# Thermister_Expansion_Module.net
KiCad netlist of a schematic drawn in EAGLE
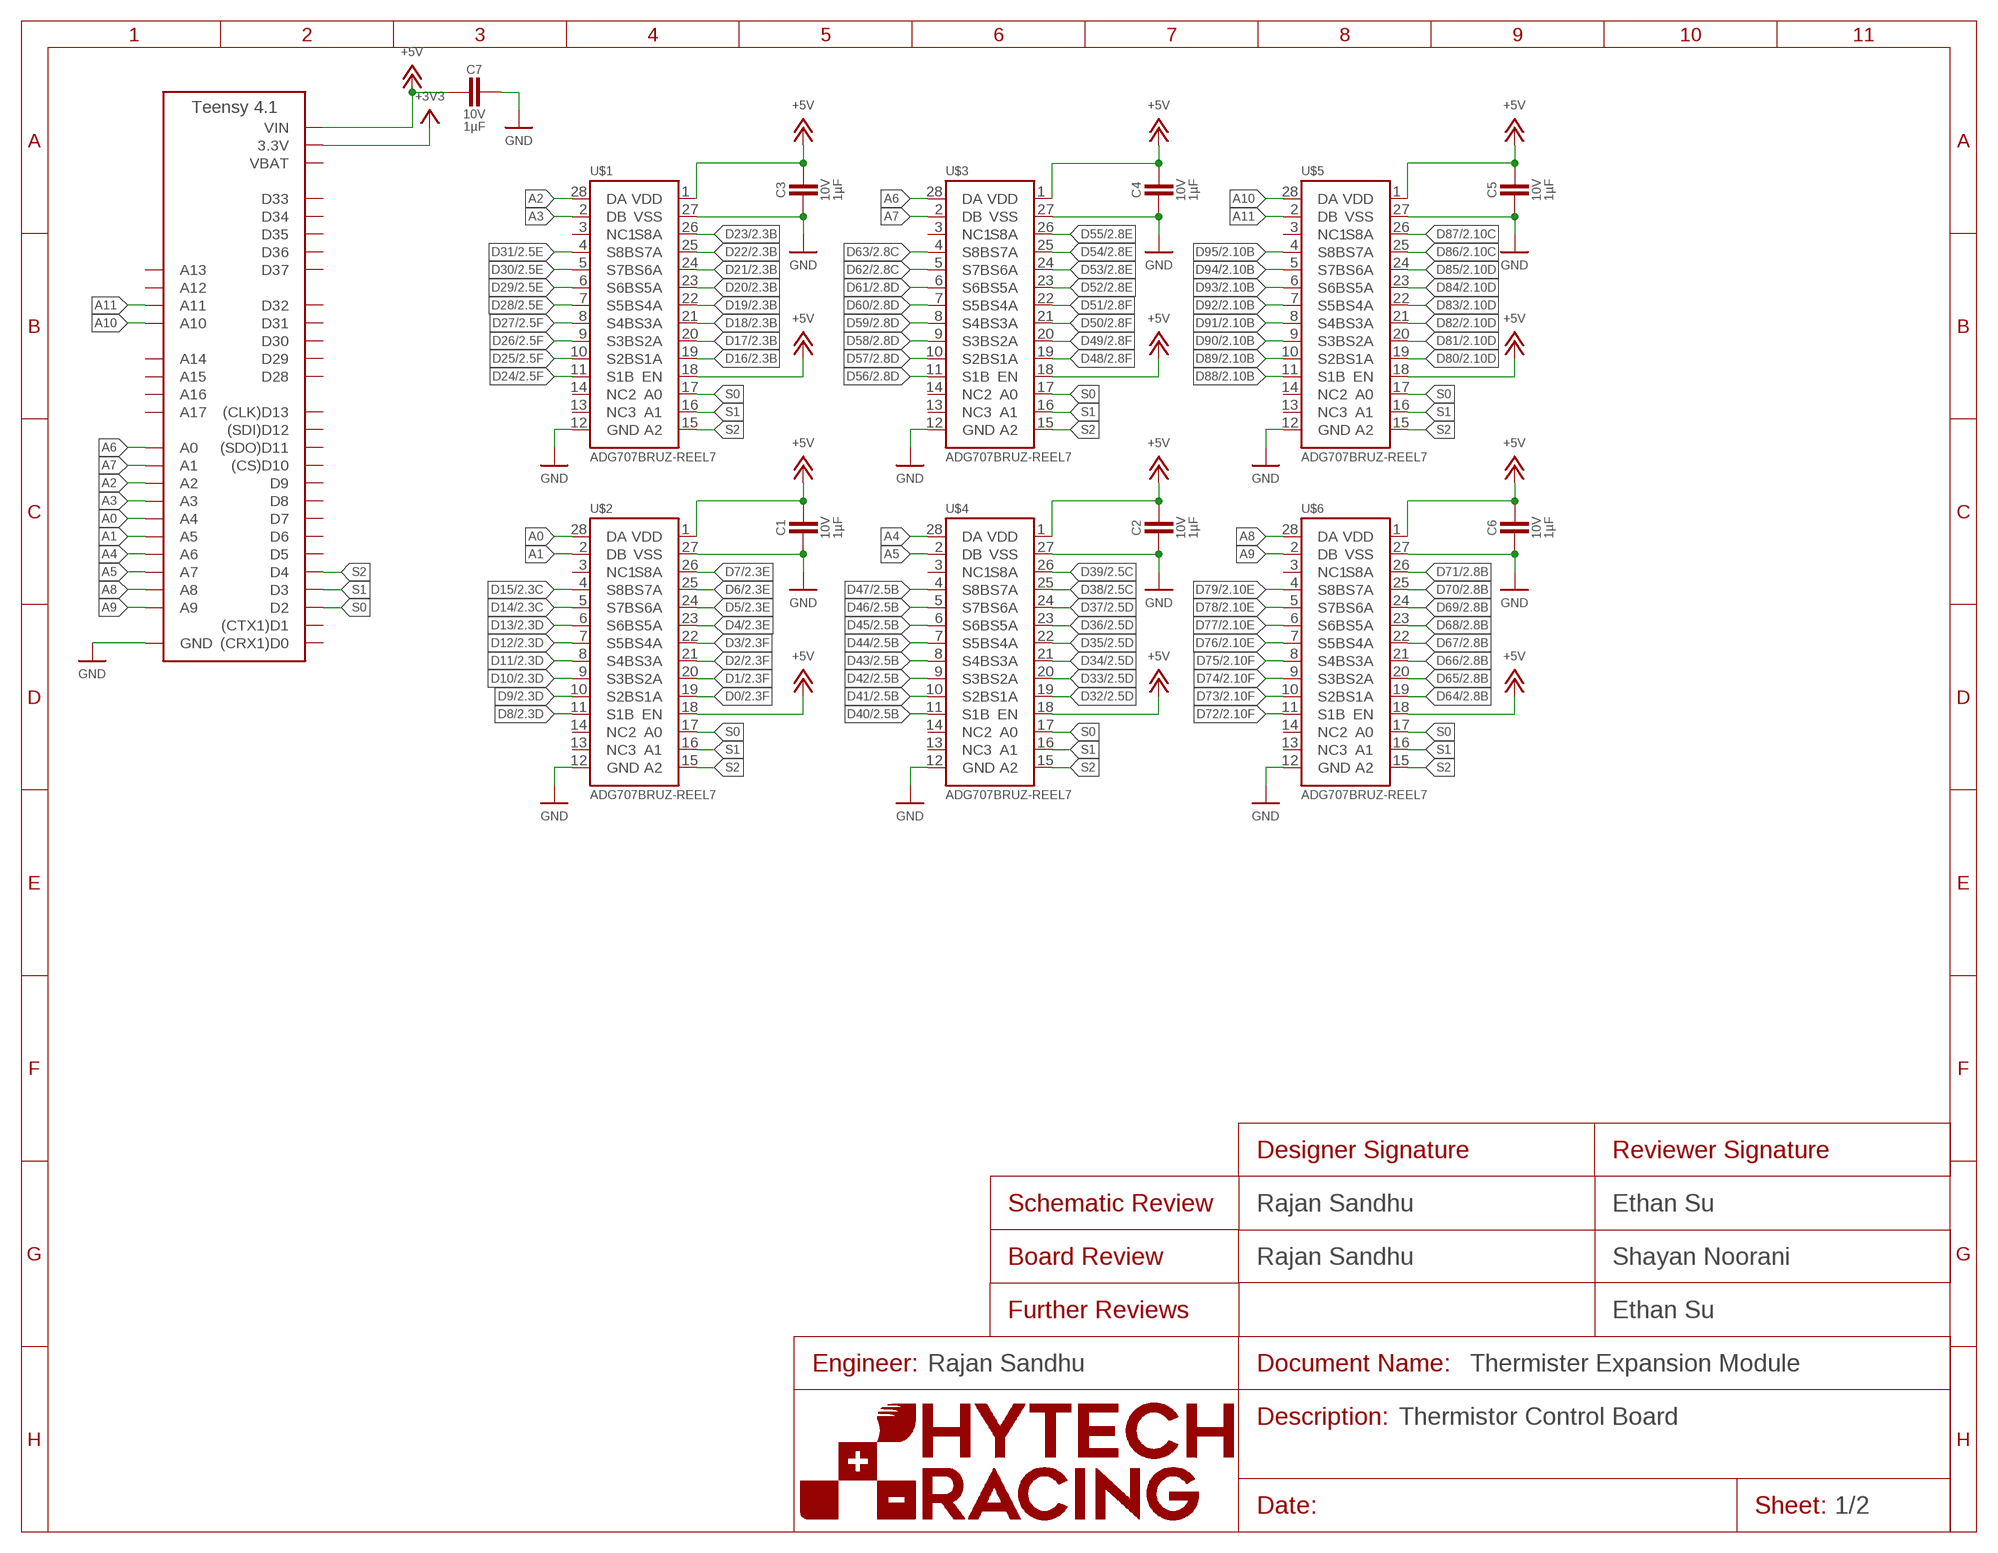
[diagram p0: schematic, sheet 1]
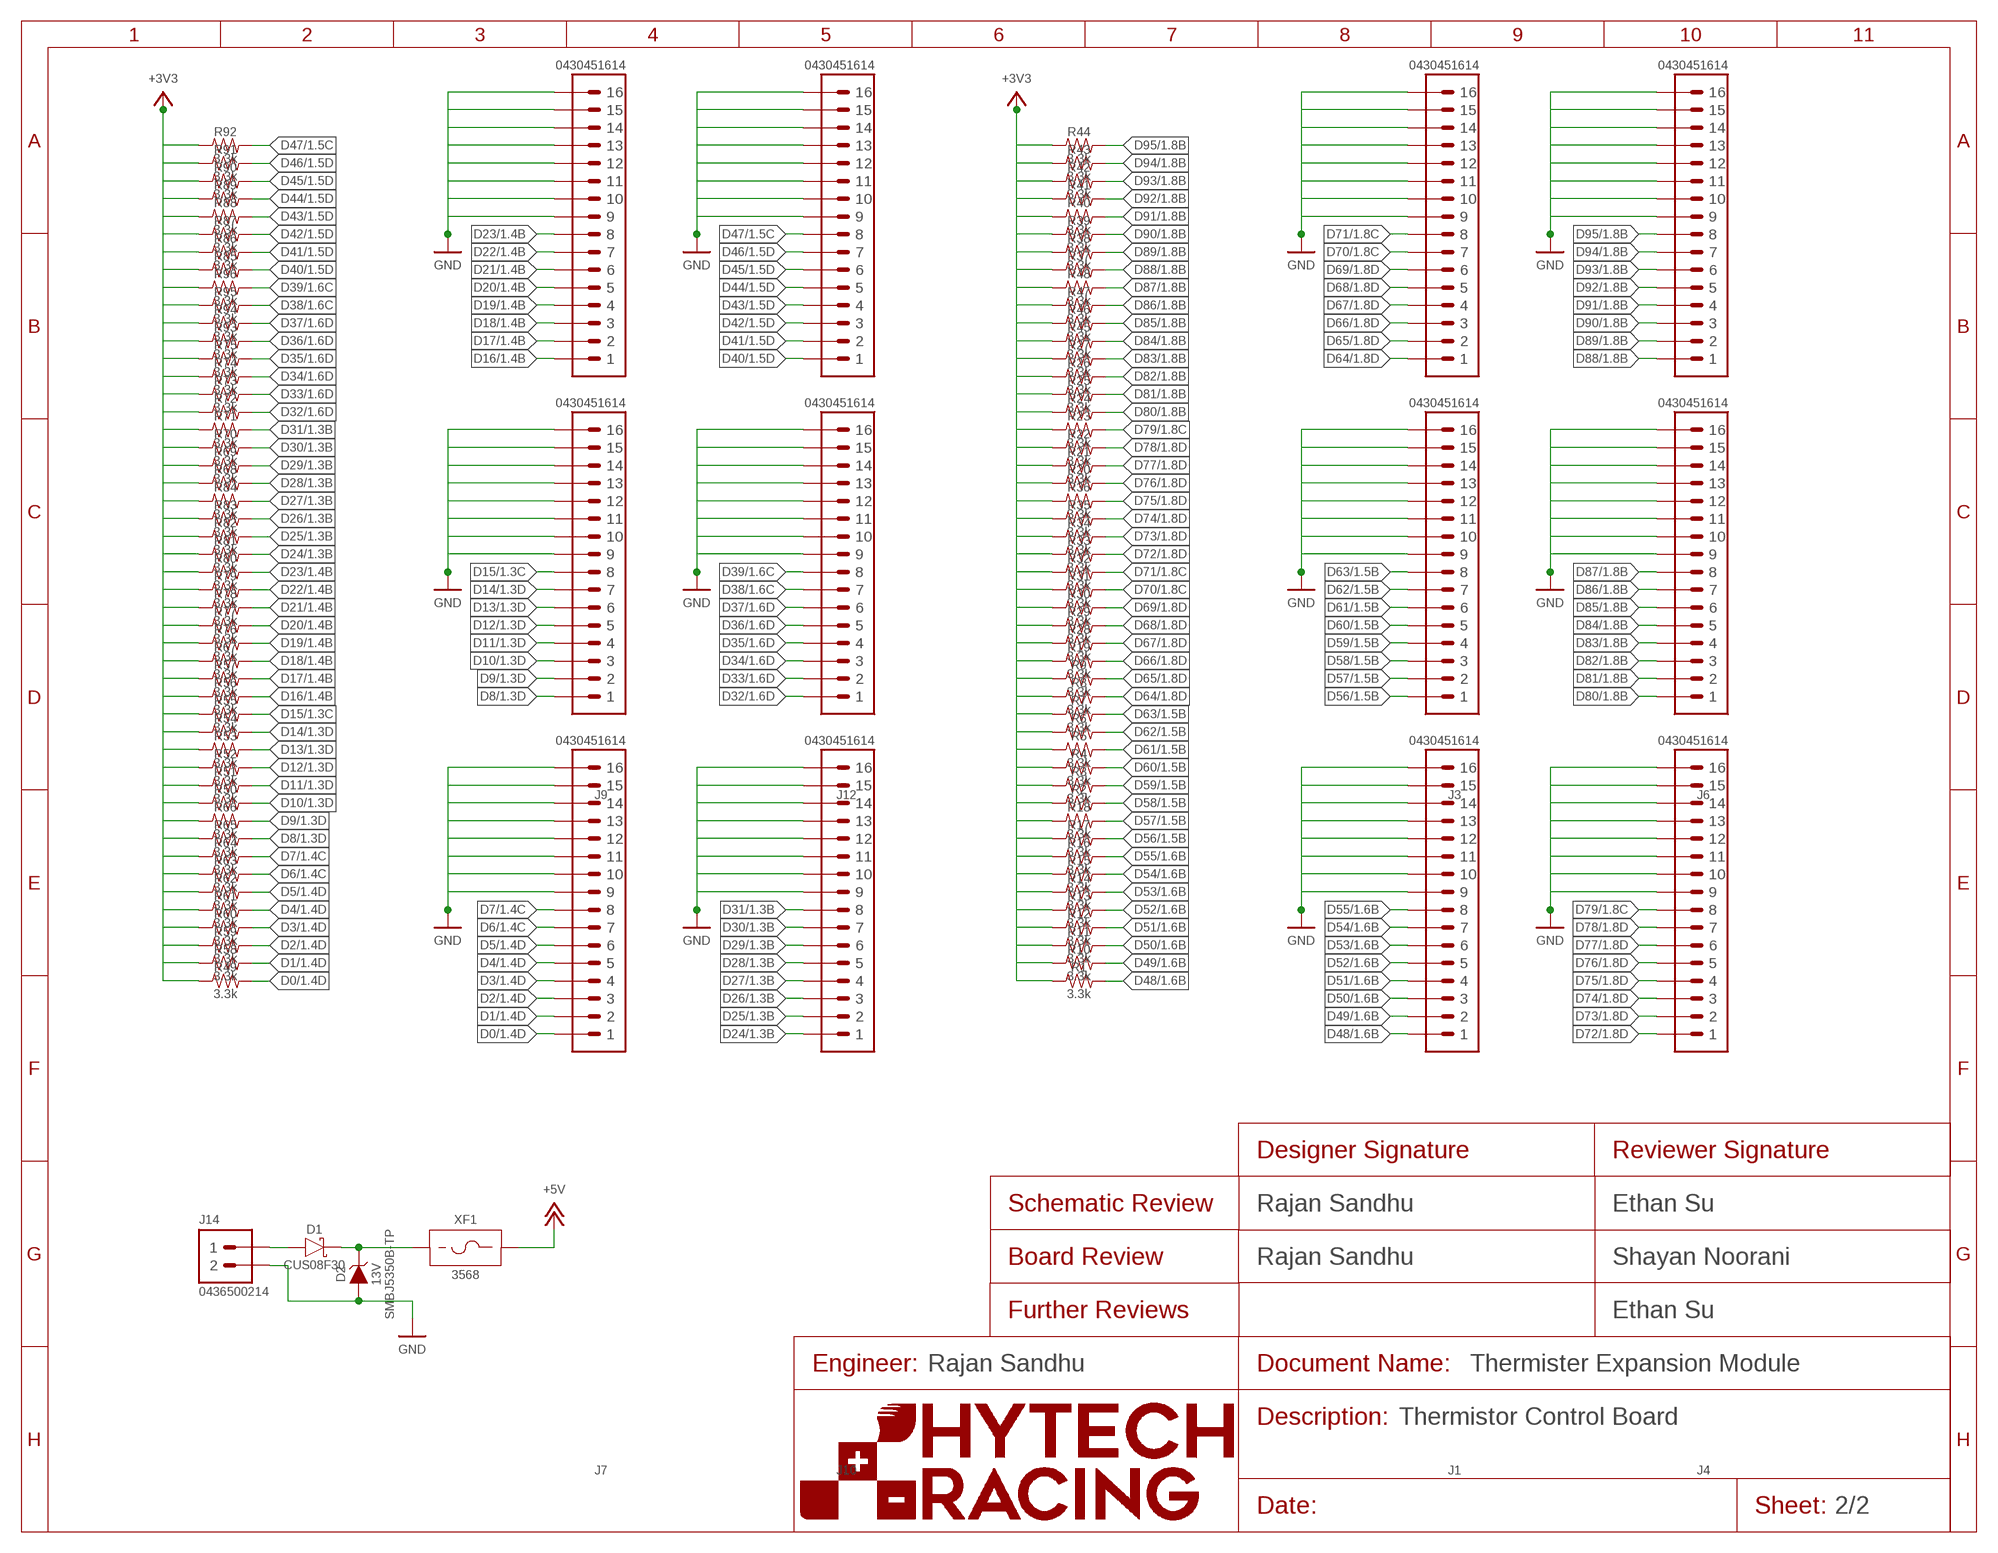
[diagram p1: schematic, sheet 2]

(export (version "E")
  (design (tool "Eeschema 10.0.6"))
  (components
    (comp (ref "D1")
      (value "SCHOTTKY_SOD323_30V")
      (footprint "eagle-import:SOD-323")
      (fields
        (field (name "MANUFACTURER") "Toshiba Semiconductor and Storage")
        (field (name "MPN") "CUS08F30")
        (field (name "VOLTAGE") "30V")
      )
      (libsource (lib "eagle-import") (part "SCHOTTKY_?_SOD32330V"))
    )
    (comp (ref "D2")
      (value "ZENER_SMB(DO-214AA)_13V")
      (footprint "eagle-import:SMB(DO-214AA)")
      (fields
        (field (name "MANUFACTURER") "Micro Commercial Co")
        (field (name "MPN") "SMBJ5350B-TP")
        (field (name "VOLTAGE") "13V")
      )
      (libsource (lib "eagle-import") (part "ZENER_?_SMB(DO-214AA)13V"))
    )
    (comp (ref "J1")
      (value "CONNECTOR-16_MF_T_V_")
      (footprint "eagle-import:MOLEX_MICROFIT_PTH_VERTICAL_16_DUAL")
      (fields (field (name "MPN") "0430451614") (field (name "MANUFACTURER") "MOLEX"))
      (libsource (lib "eagle-import") (part "CONNECTOR-16_?_MF_T_V"))
    )
    (comp (ref "J2")
      (value "CONNECTOR-16_MF_T_V_")
      (footprint "eagle-import:MOLEX_MICROFIT_PTH_VERTICAL_16_DUAL")
      (fields (field (name "MPN") "0430451614") (field (name "MANUFACTURER") "MOLEX"))
      (libsource (lib "eagle-import") (part "CONNECTOR-16_?_MF_T_V"))
    )
    (comp (ref "J3")
      (value "CONNECTOR-16_MF_T_V_")
      (footprint "eagle-import:MOLEX_MICROFIT_PTH_VERTICAL_16_DUAL")
      (fields (field (name "MPN") "0430451614") (field (name "MANUFACTURER") "MOLEX"))
      (libsource (lib "eagle-import") (part "CONNECTOR-16_?_MF_T_V"))
    )
    (comp (ref "J4")
      (value "CONNECTOR-16_MF_T_V_")
      (footprint "eagle-import:MOLEX_MICROFIT_PTH_VERTICAL_16_DUAL")
      (fields (field (name "MPN") "0430451614") (field (name "MANUFACTURER") "MOLEX"))
      (libsource (lib "eagle-import") (part "CONNECTOR-16_?_MF_T_V"))
    )
    (comp (ref "J5")
      (value "CONNECTOR-16_MF_T_V_")
      (footprint "eagle-import:MOLEX_MICROFIT_PTH_VERTICAL_16_DUAL")
      (fields (field (name "MPN") "0430451614") (field (name "MANUFACTURER") "MOLEX"))
      (libsource (lib "eagle-import") (part "CONNECTOR-16_?_MF_T_V"))
    )
    (comp (ref "J6")
      (value "CONNECTOR-16_MF_T_V_")
      (footprint "eagle-import:MOLEX_MICROFIT_PTH_VERTICAL_16_DUAL")
      (fields (field (name "MPN") "0430451614") (field (name "MANUFACTURER") "MOLEX"))
      (libsource (lib "eagle-import") (part "CONNECTOR-16_?_MF_T_V"))
    )
    (comp (ref "J7")
      (value "CONNECTOR-16_MF_T_V_")
      (footprint "eagle-import:MOLEX_MICROFIT_PTH_VERTICAL_16_DUAL")
      (fields (field (name "MPN") "0430451614") (field (name "MANUFACTURER") "MOLEX"))
      (libsource (lib "eagle-import") (part "CONNECTOR-16_?_MF_T_V"))
    )
    (comp (ref "J8")
      (value "CONNECTOR-16_MF_T_V_")
      (footprint "eagle-import:MOLEX_MICROFIT_PTH_VERTICAL_16_DUAL")
      (fields (field (name "MPN") "0430451614") (field (name "MANUFACTURER") "MOLEX"))
      (libsource (lib "eagle-import") (part "CONNECTOR-16_?_MF_T_V"))
    )
    (comp (ref "J9")
      (value "CONNECTOR-16_MF_T_V_")
      (footprint "eagle-import:MOLEX_MICROFIT_PTH_VERTICAL_16_DUAL")
      (fields (field (name "MPN") "0430451614") (field (name "MANUFACTURER") "MOLEX"))
      (libsource (lib "eagle-import") (part "CONNECTOR-16_?_MF_T_V"))
    )
    (comp (ref "J10")
      (value "CONNECTOR-16_MF_T_V_")
      (footprint "eagle-import:MOLEX_MICROFIT_PTH_VERTICAL_16_DUAL")
      (fields (field (name "MPN") "0430451614") (field (name "MANUFACTURER") "MOLEX"))
      (libsource (lib "eagle-import") (part "CONNECTOR-16_?_MF_T_V"))
    )
    (comp (ref "J11")
      (value "CONNECTOR-16_MF_T_V_")
      (footprint "eagle-import:MOLEX_MICROFIT_PTH_VERTICAL_16_DUAL")
      (fields (field (name "MPN") "0430451614") (field (name "MANUFACTURER") "MOLEX"))
      (libsource (lib "eagle-import") (part "CONNECTOR-16_?_MF_T_V"))
    )
    (comp (ref "J12")
      (value "CONNECTOR-16_MF_T_V_")
      (footprint "eagle-import:MOLEX_MICROFIT_PTH_VERTICAL_16_DUAL")
      (fields (field (name "MPN") "0430451614") (field (name "MANUFACTURER") "MOLEX"))
      (libsource (lib "eagle-import") (part "CONNECTOR-16_?_MF_T_V"))
    )
    (comp (ref "J14")
      (value "CONNECTOR-2_MICROFIT_SMD_RIGHTANGLE_02_SINGLE_BLACK")
      (footprint "eagle-import:MOLEX_MICROFIT_SMD_RIGHTANGLE_02_SINGLE")
      (fields (field (name "MANUFACTURER") "Molex") (field (name "MPN") "0436500214"))
      (libsource (lib "eagle-import") (part "CONNECTOR-2_?_MICROFIT_SMD_RIGHTANGLE_02_SINGLEBLACK"))
    )
    (comp (ref "R1")
      (value "RESISTOR_0603_3.3K")
      (footprint "eagle-import:0603-RES")
      (fields
        (field (name "MANUFACTURER") "Panasonic Electronic Components")
        (field (name "MPN") "ERJ-PB3D3301V")
        (field (name "POWER") "0.3W")
        (field (name "RESISTANCE") "3.3k")
      )
      (libsource (lib "eagle-import") (part "RESISTOR_?_06033.3K"))
    )
    (comp (ref "R2")
      (value "RESISTOR_0603_3.3K")
      (footprint "eagle-import:0603-RES")
      (fields
        (field (name "MANUFACTURER") "Panasonic Electronic Components")
        (field (name "MPN") "ERJ-PB3D3301V")
        (field (name "POWER") "0.3W")
      )
      (libsource (lib "eagle-import") (part "RESISTOR_?_06033.3K"))
    )
    (comp (ref "R3")
      (value "RESISTOR_0603_3.3K")
      (footprint "eagle-import:0603-RES")
      (fields
        (field (name "MANUFACTURER") "Panasonic Electronic Components")
        (field (name "MPN") "ERJ-PB3D3301V")
        (field (name "POWER") "0.3W")
        (field (name "RESISTANCE") "3.3k")
      )
      (libsource (lib "eagle-import") (part "RESISTOR_?_06033.3K"))
    )
    (comp (ref "R4")
      (value "RESISTOR_0603_3.3K")
      (footprint "eagle-import:0603-RES")
      (fields
        (field (name "MANUFACTURER") "Panasonic Electronic Components")
        (field (name "MPN") "ERJ-PB3D3301V")
        (field (name "POWER") "0.3W")
        (field (name "RESISTANCE") "3.3k")
      )
      (libsource (lib "eagle-import") (part "RESISTOR_?_06033.3K"))
    )
    (comp (ref "R5")
      (value "RESISTOR_0603_3.3K")
      (footprint "eagle-import:0603-RES")
      (fields
        (field (name "MANUFACTURER") "Panasonic Electronic Components")
        (field (name "MPN") "ERJ-PB3D3301V")
        (field (name "POWER") "0.3W")
        (field (name "RESISTANCE") "3.3k")
      )
      (libsource (lib "eagle-import") (part "RESISTOR_?_06033.3K"))
    )
    (comp (ref "R6")
      (value "RESISTOR_0603_3.3K")
      (footprint "eagle-import:0603-RES")
      (fields
        (field (name "MANUFACTURER") "Panasonic Electronic Components")
        (field (name "MPN") "ERJ-PB3D3301V")
        (field (name "POWER") "0.3W")
      )
      (libsource (lib "eagle-import") (part "RESISTOR_?_06033.3K"))
    )
    (comp (ref "R7")
      (value "RESISTOR_0603_3.3K")
      (footprint "eagle-import:0603-RES")
      (fields
        (field (name "MANUFACTURER") "Panasonic Electronic Components")
        (field (name "MPN") "ERJ-PB3D3301V")
        (field (name "POWER") "0.3W")
        (field (name "RESISTANCE") "3.3k")
      )
      (libsource (lib "eagle-import") (part "RESISTOR_?_06033.3K"))
    )
    (comp (ref "R8")
      (value "RESISTOR_0603_3.3K")
      (footprint "eagle-import:0603-RES")
      (fields
        (field (name "MANUFACTURER") "Panasonic Electronic Components")
        (field (name "MPN") "ERJ-PB3D3301V")
        (field (name "POWER") "0.3W")
        (field (name "RESISTANCE") "3.3k")
      )
      (libsource (lib "eagle-import") (part "RESISTOR_?_06033.3K"))
    )
    (comp (ref "R9")
      (value "RESISTOR_0603_3.3K")
      (footprint "eagle-import:0603-RES")
      (fields
        (field (name "MANUFACTURER") "Panasonic Electronic Components")
        (field (name "MPN") "ERJ-PB3D3301V")
        (field (name "POWER") "0.3W")
        (field (name "RESISTANCE") "3.3k")
      )
      (libsource (lib "eagle-import") (part "RESISTOR_?_06033.3K"))
    )
    (comp (ref "R10")
      (value "RESISTOR_0603_3.3K")
      (footprint "eagle-import:0603-RES")
      (fields
        (field (name "MANUFACTURER") "Panasonic Electronic Components")
        (field (name "MPN") "ERJ-PB3D3301V")
        (field (name "POWER") "0.3W")
        (field (name "RESISTANCE") "3.3k")
      )
      (libsource (lib "eagle-import") (part "RESISTOR_?_06033.3K"))
    )
    (comp (ref "R11")
      (value "RESISTOR_0603_3.3K")
      (footprint "eagle-import:0603-RES")
      (fields
        (field (name "MANUFACTURER") "Panasonic Electronic Components")
        (field (name "MPN") "ERJ-PB3D3301V")
        (field (name "POWER") "0.3W")
        (field (name "RESISTANCE") "3.3k")
      )
      (libsource (lib "eagle-import") (part "RESISTOR_?_06033.3K"))
    )
    (comp (ref "R12")
      (value "RESISTOR_0603_3.3K")
      (footprint "eagle-import:0603-RES")
      (fields
        (field (name "MANUFACTURER") "Panasonic Electronic Components")
        (field (name "MPN") "ERJ-PB3D3301V")
        (field (name "POWER") "0.3W")
        (field (name "RESISTANCE") "3.3k")
      )
      (libsource (lib "eagle-import") (part "RESISTOR_?_06033.3K"))
    )
    (comp (ref "R13")
      (value "RESISTOR_0603_3.3K")
      (footprint "eagle-import:0603-RES")
      (fields
        (field (name "MANUFACTURER") "Panasonic Electronic Components")
        (field (name "MPN") "ERJ-PB3D3301V")
        (field (name "POWER") "0.3W")
        (field (name "RESISTANCE") "3.3k")
      )
      (libsource (lib "eagle-import") (part "RESISTOR_?_06033.3K"))
    )
    (comp (ref "R14")
      (value "RESISTOR_0603_3.3K")
      (footprint "eagle-import:0603-RES")
      (fields
        (field (name "MANUFACTURER") "Panasonic Electronic Components")
        (field (name "MPN") "ERJ-PB3D3301V")
        (field (name "POWER") "0.3W")
        (field (name "RESISTANCE") "3.3k")
      )
      (libsource (lib "eagle-import") (part "RESISTOR_?_06033.3K"))
    )
    (comp (ref "R15")
      (value "RESISTOR_0603_3.3K")
      (footprint "eagle-import:0603-RES")
      (fields
        (field (name "MANUFACTURER") "Panasonic Electronic Components")
        (field (name "MPN") "ERJ-PB3D3301V")
        (field (name "POWER") "0.3W")
        (field (name "RESISTANCE") "3.3k")
      )
      (libsource (lib "eagle-import") (part "RESISTOR_?_06033.3K"))
    )
    (comp (ref "R16")
      (value "RESISTOR_0603_3.3K")
      (footprint "eagle-import:0603-RES")
      (fields
        (field (name "MANUFACTURER") "Panasonic Electronic Components")
        (field (name "MPN") "ERJ-PB3D3301V")
        (field (name "POWER") "0.3W")
        (field (name "RESISTANCE") "3.3k")
      )
      (libsource (lib "eagle-import") (part "RESISTOR_?_06033.3K"))
    )
    (comp (ref "R17")
      (value "RESISTOR_0603_3.3K")
      (footprint "eagle-import:0603-RES")
      (fields
        (field (name "MANUFACTURER") "Panasonic Electronic Components")
        (field (name "MPN") "ERJ-PB3D3301V")
        (field (name "POWER") "0.3W")
        (field (name "RESISTANCE") "3.3k")
      )
      (libsource (lib "eagle-import") (part "RESISTOR_?_06033.3K"))
    )
    (comp (ref "R18")
      (value "RESISTOR_0603_3.3K")
      (footprint "eagle-import:0603-RES")
      (fields
        (field (name "MANUFACTURER") "Panasonic Electronic Components")
        (field (name "MPN") "ERJ-PB3D3301V")
        (field (name "POWER") "0.3W")
        (field (name "RESISTANCE") "3.3k")
      )
      (libsource (lib "eagle-import") (part "RESISTOR_?_06033.3K"))
    )
    (comp (ref "R19")
      (value "RESISTOR_0603_3.3K")
      (footprint "eagle-import:0603-RES")
      (fields
        (field (name "MANUFACTURER") "Panasonic Electronic Components")
        (field (name "MPN") "ERJ-PB3D3301V")
        (field (name "POWER") "0.3W")
        (field (name "RESISTANCE") "3.3k")
      )
      (libsource (lib "eagle-import") (part "RESISTOR_?_06033.3K"))
    )
    (comp (ref "R20")
      (value "RESISTOR_0603_3.3K")
      (footprint "eagle-import:0603-RES")
      (fields
        (field (name "MANUFACTURER") "Panasonic Electronic Components")
        (field (name "MPN") "ERJ-PB3D3301V")
        (field (name "POWER") "0.3W")
      )
      (libsource (lib "eagle-import") (part "RESISTOR_?_06033.3K"))
    )
    (comp (ref "R21")
      (value "RESISTOR_0603_3.3K")
      (footprint "eagle-import:0603-RES")
      (fields
        (field (name "MANUFACTURER") "Panasonic Electronic Components")
        (field (name "MPN") "ERJ-PB3D3301V")
        (field (name "POWER") "0.3W")
        (field (name "RESISTANCE") "3.3k")
      )
      (libsource (lib "eagle-import") (part "RESISTOR_?_06033.3K"))
    )
    (comp (ref "R22")
      (value "RESISTOR_0603_3.3K")
      (footprint "eagle-import:0603-RES")
      (fields
        (field (name "MANUFACTURER") "Panasonic Electronic Components")
        (field (name "MPN") "ERJ-PB3D3301V")
        (field (name "POWER") "0.3W")
        (field (name "RESISTANCE") "3.3k")
      )
      (libsource (lib "eagle-import") (part "RESISTOR_?_06033.3K"))
    )
    (comp (ref "R23")
      (value "RESISTOR_0603_3.3K")
      (footprint "eagle-import:0603-RES")
      (fields
        (field (name "MANUFACTURER") "Panasonic Electronic Components")
        (field (name "MPN") "ERJ-PB3D3301V")
        (field (name "POWER") "0.3W")
        (field (name "RESISTANCE") "3.3k")
      )
      (libsource (lib "eagle-import") (part "RESISTOR_?_06033.3K"))
    )
    (comp (ref "R24")
      (value "RESISTOR_0603_3.3K")
      (footprint "eagle-import:0603-RES")
      (fields
        (field (name "MANUFACTURER") "Panasonic Electronic Components")
        (field (name "MPN") "ERJ-PB3D3301V")
        (field (name "POWER") "0.3W")
      )
      (libsource (lib "eagle-import") (part "RESISTOR_?_06033.3K"))
    )
    (comp (ref "R25")
      (value "RESISTOR_0603_3.3K")
      (footprint "eagle-import:0603-RES")
      (fields
        (field (name "MANUFACTURER") "Panasonic Electronic Components")
        (field (name "MPN") "ERJ-PB3D3301V")
        (field (name "POWER") "0.3W")
        (field (name "RESISTANCE") "3.3k")
      )
      (libsource (lib "eagle-import") (part "RESISTOR_?_06033.3K"))
    )
    (comp (ref "R26")
      (value "RESISTOR_0603_3.3K")
      (footprint "eagle-import:0603-RES")
      (fields
        (field (name "MANUFACTURER") "Panasonic Electronic Components")
        (field (name "MPN") "ERJ-PB3D3301V")
        (field (name "POWER") "0.3W")
        (field (name "RESISTANCE") "3.3k")
      )
      (libsource (lib "eagle-import") (part "RESISTOR_?_06033.3K"))
    )
    (comp (ref "R27")
      (value "RESISTOR_0603_3.3K")
      (footprint "eagle-import:0603-RES")
      (fields
        (field (name "MANUFACTURER") "Panasonic Electronic Components")
        (field (name "MPN") "ERJ-PB3D3301V")
        (field (name "POWER") "0.3W")
        (field (name "RESISTANCE") "3.3k")
      )
      (libsource (lib "eagle-import") (part "RESISTOR_?_06033.3K"))
    )
    (comp (ref "R28")
      (value "RESISTOR_0603_3.3K")
      (footprint "eagle-import:0603-RES")
      (fields
        (field (name "MANUFACTURER") "Panasonic Electronic Components")
        (field (name "MPN") "ERJ-PB3D3301V")
        (field (name "POWER") "0.3W")
        (field (name "RESISTANCE") "3.3k")
      )
      (libsource (lib "eagle-import") (part "RESISTOR_?_06033.3K"))
    )
    (comp (ref "R29")
      (value "RESISTOR_0603_3.3K")
      (footprint "eagle-import:0603-RES")
      (fields
        (field (name "MANUFACTURER") "Panasonic Electronic Components")
        (field (name "MPN") "ERJ-PB3D3301V")
        (field (name "POWER") "0.3W")
        (field (name "RESISTANCE") "3.3k")
      )
      (libsource (lib "eagle-import") (part "RESISTOR_?_06033.3K"))
    )
    (comp (ref "R30")
      (value "RESISTOR_0603_3.3K")
      (footprint "eagle-import:0603-RES")
      (fields
        (field (name "MANUFACTURER") "Panasonic Electronic Components")
        (field (name "MPN") "ERJ-PB3D3301V")
        (field (name "POWER") "0.3W")
        (field (name "RESISTANCE") "3.3k")
      )
      (libsource (lib "eagle-import") (part "RESISTOR_?_06033.3K"))
    )
    (comp (ref "R31")
      (value "RESISTOR_0603_3.3K")
      (footprint "eagle-import:0603-RES")
      (fields
        (field (name "MANUFACTURER") "Panasonic Electronic Components")
        (field (name "MPN") "ERJ-PB3D3301V")
        (field (name "POWER") "0.3W")
        (field (name "RESISTANCE") "3.3k")
      )
      (libsource (lib "eagle-import") (part "RESISTOR_?_06033.3K"))
    )
    (comp (ref "R32")
      (value "RESISTOR_0603_3.3K")
      (footprint "eagle-import:0603-RES")
      (fields
        (field (name "MANUFACTURER") "Panasonic Electronic Components")
        (field (name "MPN") "ERJ-PB3D3301V")
        (field (name "POWER") "0.3W")
        (field (name "RESISTANCE") "3.3k")
      )
      (libsource (lib "eagle-import") (part "RESISTOR_?_06033.3K"))
    )
    (comp (ref "R33")
      (value "RESISTOR_0603_3.3K")
      (footprint "eagle-import:0603-RES")
      (fields
        (field (name "MANUFACTURER") "Panasonic Electronic Components")
        (field (name "MPN") "ERJ-PB3D3301V")
        (field (name "POWER") "0.3W")
        (field (name "RESISTANCE") "3.3k")
      )
      (libsource (lib "eagle-import") (part "RESISTOR_?_06033.3K"))
    )
    (comp (ref "R34")
      (value "RESISTOR_0603_3.3K")
      (footprint "eagle-import:0603-RES")
      (fields
        (field (name "MANUFACTURER") "Panasonic Electronic Components")
        (field (name "MPN") "ERJ-PB3D3301V")
        (field (name "POWER") "0.3W")
        (field (name "RESISTANCE") "3.3k")
      )
      (libsource (lib "eagle-import") (part "RESISTOR_?_06033.3K"))
    )
    (comp (ref "R35")
      (value "RESISTOR_0603_3.3K")
      (footprint "eagle-import:0603-RES")
      (fields
        (field (name "MANUFACTURER") "Panasonic Electronic Components")
        (field (name "MPN") "ERJ-PB3D3301V")
        (field (name "POWER") "0.3W")
        (field (name "RESISTANCE") "3.3k")
      )
      (libsource (lib "eagle-import") (part "RESISTOR_?_06033.3K"))
    )
    (comp (ref "R36")
      (value "RESISTOR_0603_3.3K")
      (footprint "eagle-import:0603-RES")
      (fields
        (field (name "MANUFACTURER") "Panasonic Electronic Components")
        (field (name "MPN") "ERJ-PB3D3301V")
        (field (name "POWER") "0.3W")
        (field (name "RESISTANCE") "3.3k")
      )
      (libsource (lib "eagle-import") (part "RESISTOR_?_06033.3K"))
    )
    (comp (ref "R37")
      (value "RESISTOR_0603_3.3K")
      (footprint "eagle-import:0603-RES")
      (fields
        (field (name "MANUFACTURER") "Panasonic Electronic Components")
        (field (name "MPN") "ERJ-PB3D3301V")
        (field (name "POWER") "0.3W")
      )
      (libsource (lib "eagle-import") (part "RESISTOR_?_06033.3K"))
    )
    (comp (ref "R38")
      (value "RESISTOR_0603_3.3K")
      (footprint "eagle-import:0603-RES")
      (fields
        (field (name "MANUFACTURER") "Panasonic Electronic Components")
        (field (name "MPN") "ERJ-PB3D3301V")
        (field (name "POWER") "0.3W")
        (field (name "RESISTANCE") "3.3k")
      )
      (libsource (lib "eagle-import") (part "RESISTOR_?_06033.3K"))
    )
    (comp (ref "R39")
      (value "RESISTOR_0603_3.3K")
      (footprint "eagle-import:0603-RES")
      (fields
        (field (name "MANUFACTURER") "Panasonic Electronic Components")
        (field (name "MPN") "ERJ-PB3D3301V")
        (field (name "POWER") "0.3W")
        (field (name "RESISTANCE") "3.3k")
      )
      (libsource (lib "eagle-import") (part "RESISTOR_?_06033.3K"))
    )
    (comp (ref "R40")
      (value "RESISTOR_0603_3.3K")
      (footprint "eagle-import:0603-RES")
      (fields
        (field (name "MANUFACTURER") "Panasonic Electronic Components")
        (field (name "MPN") "ERJ-PB3D3301V")
        (field (name "POWER") "0.3W")
        (field (name "RESISTANCE") "3.3k")
      )
      (libsource (lib "eagle-import") (part "RESISTOR_?_06033.3K"))
    )
    (comp (ref "R41")
      (value "RESISTOR_0603_3.3K")
      (footprint "eagle-import:0603-RES")
      (fields
        (field (name "MANUFACTURER") "Panasonic Electronic Components")
        (field (name "MPN") "ERJ-PB3D3301V")
        (field (name "POWER") "0.3W")
      )
      (libsource (lib "eagle-import") (part "RESISTOR_?_06033.3K"))
    )
    (comp (ref "R42")
      (value "RESISTOR_0603_3.3K")
      (footprint "eagle-import:0603-RES")
      (fields
        (field (name "MANUFACTURER") "Panasonic Electronic Components")
        (field (name "MPN") "ERJ-PB3D3301V")
        (field (name "POWER") "0.3W")
        (field (name "RESISTANCE") "3.3k")
      )
      (libsource (lib "eagle-import") (part "RESISTOR_?_06033.3K"))
    )
    (comp (ref "R43")
      (value "RESISTOR_0603_3.3K")
      (footprint "eagle-import:0603-RES")
      (fields
        (field (name "MANUFACTURER") "Panasonic Electronic Components")
        (field (name "MPN") "ERJ-PB3D3301V")
        (field (name "POWER") "0.3W")
        (field (name "RESISTANCE") "3.3k")
      )
      (libsource (lib "eagle-import") (part "RESISTOR_?_06033.3K"))
    )
    (comp (ref "R44")
      (value "RESISTOR_0603_3.3K")
      (footprint "eagle-import:0603-RES")
      (fields
        (field (name "MANUFACTURER") "Panasonic Electronic Components")
        (field (name "MPN") "ERJ-PB3D3301V")
        (field (name "POWER") "0.3W")
        (field (name "RESISTANCE") "3.3k")
      )
      (libsource (lib "eagle-import") (part "RESISTOR_?_06033.3K"))
    )
    (comp (ref "R45")
      (value "RESISTOR_0603_3.3K")
      (footprint "eagle-import:0603-RES")
      (fields
        (field (name "MANUFACTURER") "Panasonic Electronic Components")
        (field (name "MPN") "ERJ-PB3D3301V")
        (field (name "POWER") "0.3W")
        (field (name "RESISTANCE") "3.3k")
      )
      (libsource (lib "eagle-import") (part "RESISTOR_?_06033.3K"))
    )
    (comp (ref "R46")
      (value "RESISTOR_0603_3.3K")
      (footprint "eagle-import:0603-RES")
      (fields
        (field (name "MANUFACTURER") "Panasonic Electronic Components")
        (field (name "MPN") "ERJ-PB3D3301V")
        (field (name "POWER") "0.3W")
        (field (name "RESISTANCE") "3.3k")
      )
      (libsource (lib "eagle-import") (part "RESISTOR_?_06033.3K"))
    )
    (comp (ref "R47")
      (value "RESISTOR_0603_3.3K")
      (footprint "eagle-import:0603-RES")
      (fields
        (field (name "MANUFACTURER") "Panasonic Electronic Components")
        (field (name "MPN") "ERJ-PB3D3301V")
        (field (name "POWER") "0.3W")
        (field (name "RESISTANCE") "3.3k")
      )
      (libsource (lib "eagle-import") (part "RESISTOR_?_06033.3K"))
    )
    (comp (ref "R48")
      (value "RESISTOR_0603_3.3K")
      (footprint "eagle-import:0603-RES")
      (fields
        (field (name "MANUFACTURER") "Panasonic Electronic Components")
        (field (name "MPN") "ERJ-PB3D3301V")
        (field (name "POWER") "0.3W")
        (field (name "RESISTANCE") "3.3k")
      )
      (libsource (lib "eagle-import") (part "RESISTOR_?_06033.3K"))
    )
    (comp (ref "R49")
      (value "RESISTOR_0603_3.3K")
      (footprint "eagle-import:0603-RES")
      (fields
        (field (name "MANUFACTURER") "Panasonic Electronic Components")
        (field (name "MPN") "ERJ-PB3D3301V")
        (field (name "POWER") "0.3W")
        (field (name "RESISTANCE") "3.3k")
      )
      (libsource (lib "eagle-import") (part "RESISTOR_?_06033.3K"))
    )
    (comp (ref "R50")
      (value "RESISTOR_0603_3.3K")
      (footprint "eagle-import:0603-RES")
      (fields
        (field (name "MANUFACTURER") "Panasonic Electronic Components")
        (field (name "MPN") "ERJ-PB3D3301V")
        (field (name "POWER") "0.3W")
      )
      (libsource (lib "eagle-import") (part "RESISTOR_?_06033.3K"))
    )
    (comp (ref "R51")
      (value "RESISTOR_0603_3.3K")
      (footprint "eagle-import:0603-RES")
      (fields
        (field (name "MANUFACTURER") "Panasonic Electronic Components")
        (field (name "MPN") "ERJ-PB3D3301V")
        (field (name "POWER") "0.3W")
        (field (name "RESISTANCE") "3.3k")
      )
      (libsource (lib "eagle-import") (part "RESISTOR_?_06033.3K"))
    )
    (comp (ref "R52")
      (value "RESISTOR_0603_3.3K")
      (footprint "eagle-import:0603-RES")
      (fields
        (field (name "MANUFACTURER") "Panasonic Electronic Components")
        (field (name "MPN") "ERJ-PB3D3301V")
        (field (name "POWER") "0.3W")
        (field (name "RESISTANCE") "3.3k")
      )
      (libsource (lib "eagle-import") (part "RESISTOR_?_06033.3K"))
    )
    (comp (ref "R53")
      (value "RESISTOR_0603_3.3K")
      (footprint "eagle-import:0603-RES")
      (fields
        (field (name "MANUFACTURER") "Panasonic Electronic Components")
        (field (name "MPN") "ERJ-PB3D3301V")
        (field (name "POWER") "0.3W")
        (field (name "RESISTANCE") "3.3k")
      )
      (libsource (lib "eagle-import") (part "RESISTOR_?_06033.3K"))
    )
    (comp (ref "R54")
      (value "RESISTOR_0603_3.3K")
      (footprint "eagle-import:0603-RES")
      (fields
        (field (name "MANUFACTURER") "Panasonic Electronic Components")
        (field (name "MPN") "ERJ-PB3D3301V")
        (field (name "POWER") "0.3W")
      )
      (libsource (lib "eagle-import") (part "RESISTOR_?_06033.3K"))
    )
    (comp (ref "R55")
      (value "RESISTOR_0603_3.3K")
      (footprint "eagle-import:0603-RES")
      (fields
        (field (name "MANUFACTURER") "Panasonic Electronic Components")
        (field (name "MPN") "ERJ-PB3D3301V")
        (field (name "POWER") "0.3W")
        (field (name "RESISTANCE") "3.3k")
      )
      (libsource (lib "eagle-import") (part "RESISTOR_?_06033.3K"))
    )
    (comp (ref "R56")
      (value "RESISTOR_0603_3.3K")
      (footprint "eagle-import:0603-RES")
      (fields
        (field (name "MANUFACTURER") "Panasonic Electronic Components")
        (field (name "MPN") "ERJ-PB3D3301V")
        (field (name "POWER") "0.3W")
        (field (name "RESISTANCE") "3.3k")
      )
      (libsource (lib "eagle-import") (part "RESISTOR_?_06033.3K"))
    )
    (comp (ref "R57")
      (value "RESISTOR_0603_3.3K")
      (footprint "eagle-import:0603-RES")
      (fields
        (field (name "MANUFACTURER") "Panasonic Electronic Components")
        (field (name "MPN") "ERJ-PB3D3301V")
        (field (name "POWER") "0.3W")
        (field (name "RESISTANCE") "3.3k")
      )
      (libsource (lib "eagle-import") (part "RESISTOR_?_06033.3K"))
    )
    (comp (ref "R58")
      (value "RESISTOR_0603_3.3K")
      (footprint "eagle-import:0603-RES")
      (fields
        (field (name "MANUFACTURER") "Panasonic Electronic Components")
        (field (name "MPN") "ERJ-PB3D3301V")
        (field (name "POWER") "0.3W")
        (field (name "RESISTANCE") "3.3k")
      )
      (libsource (lib "eagle-import") (part "RESISTOR_?_06033.3K"))
    )
    (comp (ref "R59")
      (value "RESISTOR_0603_3.3K")
      (footprint "eagle-import:0603-RES")
      (fields
        (field (name "MANUFACTURER") "Panasonic Electronic Components")
        (field (name "MPN") "ERJ-PB3D3301V")
        (field (name "POWER") "0.3W")
        (field (name "RESISTANCE") "3.3k")
      )
      (libsource (lib "eagle-import") (part "RESISTOR_?_06033.3K"))
    )
    (comp (ref "R60")
      (value "RESISTOR_0603_3.3K")
      (footprint "eagle-import:0603-RES")
      (fields
        (field (name "MANUFACTURER") "Panasonic Electronic Components")
        (field (name "MPN") "ERJ-PB3D3301V")
        (field (name "POWER") "0.3W")
        (field (name "RESISTANCE") "3.3k")
      )
      (libsource (lib "eagle-import") (part "RESISTOR_?_06033.3K"))
    )
    (comp (ref "R61")
      (value "RESISTOR_0603_3.3K")
      (footprint "eagle-import:0603-RES")
      (fields
        (field (name "MANUFACTURER") "Panasonic Electronic Components")
        (field (name "MPN") "ERJ-PB3D3301V")
        (field (name "POWER") "0.3W")
        (field (name "RESISTANCE") "3.3k")
      )
      (libsource (lib "eagle-import") (part "RESISTOR_?_06033.3K"))
    )
    (comp (ref "R62")
      (value "RESISTOR_0603_3.3K")
      (footprint "eagle-import:0603-RES")
      (fields
        (field (name "MANUFACTURER") "Panasonic Electronic Components")
        (field (name "MPN") "ERJ-PB3D3301V")
        (field (name "POWER") "0.3W")
        (field (name "RESISTANCE") "3.3k")
      )
      (libsource (lib "eagle-import") (part "RESISTOR_?_06033.3K"))
    )
    (comp (ref "R63")
      (value "RESISTOR_0603_3.3K")
      (footprint "eagle-import:0603-RES")
      (fields
        (field (name "MANUFACTURER") "Panasonic Electronic Components")
        (field (name "MPN") "ERJ-PB3D3301V")
        (field (name "POWER") "0.3W")
        (field (name "RESISTANCE") "3.3k")
      )
      (libsource (lib "eagle-import") (part "RESISTOR_?_06033.3K"))
    )
    (comp (ref "R64")
      (value "RESISTOR_0603_3.3K")
      (footprint "eagle-import:0603-RES")
      (fields
        (field (name "MANUFACTURER") "Panasonic Electronic Components")
        (field (name "MPN") "ERJ-PB3D3301V")
        (field (name "POWER") "0.3W")
        (field (name "RESISTANCE") "3.3k")
      )
      (libsource (lib "eagle-import") (part "RESISTOR_?_06033.3K"))
    )
    (comp (ref "R65")
      (value "RESISTOR_0603_3.3K")
      (footprint "eagle-import:0603-RES")
      (fields
        (field (name "MANUFACTURER") "Panasonic Electronic Components")
        (field (name "MPN") "ERJ-PB3D3301V")
        (field (name "POWER") "0.3W")
        (field (name "RESISTANCE") "3.3k")
      )
      (libsource (lib "eagle-import") (part "RESISTOR_?_06033.3K"))
    )
    (comp (ref "R66")
      (value "RESISTOR_0603_3.3K")
      (footprint "eagle-import:0603-RES")
      (fields
        (field (name "MANUFACTURER") "Panasonic Electronic Components")
        (field (name "MPN") "ERJ-PB3D3301V")
        (field (name "POWER") "0.3W")
        (field (name "RESISTANCE") "3.3k")
      )
      (libsource (lib "eagle-import") (part "RESISTOR_?_06033.3K"))
    )
    (comp (ref "R67")
      (value "RESISTOR_0603_3.3K")
      (footprint "eagle-import:0603-RES")
      (fields
        (field (name "MANUFACTURER") "Panasonic Electronic Components")
        (field (name "MPN") "ERJ-PB3D3301V")
        (field (name "POWER") "0.3W")
        (field (name "RESISTANCE") "3.3k")
      )
      (libsource (lib "eagle-import") (part "RESISTOR_?_06033.3K"))
    )
    (comp (ref "R68")
      (value "RESISTOR_0603_3.3K")
      (footprint "eagle-import:0603-RES")
      (fields
        (field (name "MANUFACTURER") "Panasonic Electronic Components")
        (field (name "MPN") "ERJ-PB3D3301V")
        (field (name "POWER") "0.3W")
      )
      (libsource (lib "eagle-import") (part "RESISTOR_?_06033.3K"))
    )
    (comp (ref "R69")
      (value "RESISTOR_0603_3.3K")
      (footprint "eagle-import:0603-RES")
      (fields
        (field (name "MANUFACTURER") "Panasonic Electronic Components")
        (field (name "MPN") "ERJ-PB3D3301V")
        (field (name "POWER") "0.3W")
        (field (name "RESISTANCE") "3.3k")
      )
      (libsource (lib "eagle-import") (part "RESISTOR_?_06033.3K"))
    )
    (comp (ref "R70")
      (value "RESISTOR_0603_3.3K")
      (footprint "eagle-import:0603-RES")
      (fields
        (field (name "MANUFACTURER") "Panasonic Electronic Components")
        (field (name "MPN") "ERJ-PB3D3301V")
        (field (name "POWER") "0.3W")
        (field (name "RESISTANCE") "3.3k")
      )
      (libsource (lib "eagle-import") (part "RESISTOR_?_06033.3K"))
    )
    (comp (ref "R71")
      (value "RESISTOR_0603_3.3K")
      (footprint "eagle-import:0603-RES")
      (fields
        (field (name "MANUFACTURER") "Panasonic Electronic Components")
        (field (name "MPN") "ERJ-PB3D3301V")
        (field (name "POWER") "0.3W")
        (field (name "RESISTANCE") "3.3k")
      )
      (libsource (lib "eagle-import") (part "RESISTOR_?_06033.3K"))
    )
    (comp (ref "R72")
      (value "RESISTOR_0603_3.3K")
      (footprint "eagle-import:0603-RES")
      (fields
        (field (name "MANUFACTURER") "Panasonic Electronic Components")
        (field (name "MPN") "ERJ-PB3D3301V")
        (field (name "POWER") "0.3W")
      )
      (libsource (lib "eagle-import") (part "RESISTOR_?_06033.3K"))
    )
    (comp (ref "R73")
      (value "RESISTOR_0603_3.3K")
      (footprint "eagle-import:0603-RES")
      (fields
        (field (name "MANUFACTURER") "Panasonic Electronic Components")
        (field (name "MPN") "ERJ-PB3D3301V")
        (field (name "POWER") "0.3W")
        (field (name "RESISTANCE") "3.3k")
      )
      (libsource (lib "eagle-import") (part "RESISTOR_?_06033.3K"))
    )
    (comp (ref "R74")
      (value "RESISTOR_0603_3.3K")
      (footprint "eagle-import:0603-RES")
      (fields
        (field (name "MANUFACTURER") "Panasonic Electronic Components")
        (field (name "MPN") "ERJ-PB3D3301V")
        (field (name "POWER") "0.3W")
        (field (name "RESISTANCE") "3.3k")
      )
      (libsource (lib "eagle-import") (part "RESISTOR_?_06033.3K"))
    )
    (comp (ref "R75")
      (value "RESISTOR_0603_3.3K")
      (footprint "eagle-import:0603-RES")
      (fields
        (field (name "MANUFACTURER") "Panasonic Electronic Components")
        (field (name "MPN") "ERJ-PB3D3301V")
        (field (name "POWER") "0.3W")
        (field (name "RESISTANCE") "3.3k")
      )
      (libsource (lib "eagle-import") (part "RESISTOR_?_06033.3K"))
    )
    (comp (ref "R76")
      (value "RESISTOR_0603_3.3K")
      (footprint "eagle-import:0603-RES")
      (fields
        (field (name "MANUFACTURER") "Panasonic Electronic Components")
        (field (name "MPN") "ERJ-PB3D3301V")
        (field (name "POWER") "0.3W")
        (field (name "RESISTANCE") "3.3k")
      )
      (libsource (lib "eagle-import") (part "RESISTOR_?_06033.3K"))
    )
    (comp (ref "R77")
      (value "RESISTOR_0603_3.3K")
      (footprint "eagle-import:0603-RES")
      (fields
        (field (name "MANUFACTURER") "Panasonic Electronic Components")
        (field (name "MPN") "ERJ-PB3D3301V")
        (field (name "POWER") "0.3W")
        (field (name "RESISTANCE") "3.3k")
      )
      (libsource (lib "eagle-import") (part "RESISTOR_?_06033.3K"))
    )
    (comp (ref "R78")
      (value "RESISTOR_0603_3.3K")
      (footprint "eagle-import:0603-RES")
      (fields
        (field (name "MANUFACTURER") "Panasonic Electronic Components")
        (field (name "MPN") "ERJ-PB3D3301V")
        (field (name "POWER") "0.3W")
        (field (name "RESISTANCE") "3.3k")
      )
      (libsource (lib "eagle-import") (part "RESISTOR_?_06033.3K"))
    )
    (comp (ref "R79")
      (value "RESISTOR_0603_3.3K")
      (footprint "eagle-import:0603-RES")
      (fields
        (field (name "MANUFACTURER") "Panasonic Electronic Components")
        (field (name "MPN") "ERJ-PB3D3301V")
        (field (name "POWER") "0.3W")
        (field (name "RESISTANCE") "3.3k")
      )
      (libsource (lib "eagle-import") (part "RESISTOR_?_06033.3K"))
    )
    (comp (ref "R80")
      (value "RESISTOR_0603_3.3K")
      (footprint "eagle-import:0603-RES")
      (fields
        (field (name "MANUFACTURER") "Panasonic Electronic Components")
        (field (name "MPN") "ERJ-PB3D3301V")
        (field (name "POWER") "0.3W")
        (field (name "RESISTANCE") "3.3k")
      )
      (libsource (lib "eagle-import") (part "RESISTOR_?_06033.3K"))
    )
    (comp (ref "R81")
      (value "RESISTOR_0603_3.3K")
      (footprint "eagle-import:0603-RES")
      (fields
        (field (name "MANUFACTURER") "Panasonic Electronic Components")
        (field (name "MPN") "ERJ-PB3D3301V")
        (field (name "POWER") "0.3W")
        (field (name "RESISTANCE") "3.3k")
      )
      (libsource (lib "eagle-import") (part "RESISTOR_?_06033.3K"))
    )
    (comp (ref "R82")
      (value "RESISTOR_0603_3.3K")
      (footprint "eagle-import:0603-RES")
      (fields
        (field (name "MANUFACTURER") "Panasonic Electronic Components")
        (field (name "MPN") "ERJ-PB3D3301V")
        (field (name "POWER") "0.3W")
        (field (name "RESISTANCE") "3.3k")
      )
      (libsource (lib "eagle-import") (part "RESISTOR_?_06033.3K"))
    )
    (comp (ref "R83")
      (value "RESISTOR_0603_3.3K")
      (footprint "eagle-import:0603-RES")
      (fields
        (field (name "MANUFACTURER") "Panasonic Electronic Components")
        (field (name "MPN") "ERJ-PB3D3301V")
        (field (name "POWER") "0.3W")
        (field (name "RESISTANCE") "3.3k")
      )
      (libsource (lib "eagle-import") (part "RESISTOR_?_06033.3K"))
    )
    (comp (ref "R84")
      (value "RESISTOR_0603_3.3K")
      (footprint "eagle-import:0603-RES")
      (fields
        (field (name "MANUFACTURER") "Panasonic Electronic Components")
        (field (name "MPN") "ERJ-PB3D3301V")
        (field (name "POWER") "0.3W")
        (field (name "RESISTANCE") "3.3k")
      )
      (libsource (lib "eagle-import") (part "RESISTOR_?_06033.3K"))
    )
    (comp (ref "R85")
      (value "RESISTOR_0603_3.3K")
      (footprint "eagle-import:0603-RES")
      (fields
        (field (name "MANUFACTURER") "Panasonic Electronic Components")
        (field (name "MPN") "ERJ-PB3D3301V")
        (field (name "POWER") "0.3W")
      )
      (libsource (lib "eagle-import") (part "RESISTOR_?_06033.3K"))
    )
    (comp (ref "R86")
      (value "RESISTOR_0603_3.3K")
      (footprint "eagle-import:0603-RES")
      (fields
        (field (name "MANUFACTURER") "Panasonic Electronic Components")
        (field (name "MPN") "ERJ-PB3D3301V")
        (field (name "POWER") "0.3W")
        (field (name "RESISTANCE") "3.3k")
      )
      (libsource (lib "eagle-import") (part "RESISTOR_?_06033.3K"))
    )
    (comp (ref "R87")
      (value "RESISTOR_0603_3.3K")
      (footprint "eagle-import:0603-RES")
      (fields
        (field (name "MANUFACTURER") "Panasonic Electronic Components")
        (field (name "MPN") "ERJ-PB3D3301V")
        (field (name "POWER") "0.3W")
        (field (name "RESISTANCE") "3.3k")
      )
      (libsource (lib "eagle-import") (part "RESISTOR_?_06033.3K"))
    )
    (comp (ref "R88")
      (value "RESISTOR_0603_3.3K")
      (footprint "eagle-import:0603-RES")
      (fields
        (field (name "MANUFACTURER") "Panasonic Electronic Components")
        (field (name "MPN") "ERJ-PB3D3301V")
        (field (name "POWER") "0.3W")
        (field (name "RESISTANCE") "3.3k")
      )
      (libsource (lib "eagle-import") (part "RESISTOR_?_06033.3K"))
    )
    (comp (ref "R89")
      (value "RESISTOR_0603_3.3K")
      (footprint "eagle-import:0603-RES")
      (fields
        (field (name "MANUFACTURER") "Panasonic Electronic Components")
        (field (name "MPN") "ERJ-PB3D3301V")
        (field (name "POWER") "0.3W")
      )
      (libsource (lib "eagle-import") (part "RESISTOR_?_06033.3K"))
    )
    (comp (ref "R90")
      (value "RESISTOR_0603_3.3K")
      (footprint "eagle-import:0603-RES")
      (fields
        (field (name "MANUFACTURER") "Panasonic Electronic Components")
        (field (name "MPN") "ERJ-PB3D3301V")
        (field (name "POWER") "0.3W")
        (field (name "RESISTANCE") "3.3k")
      )
      (libsource (lib "eagle-import") (part "RESISTOR_?_06033.3K"))
    )
    (comp (ref "R91")
      (value "RESISTOR_0603_3.3K")
      (footprint "eagle-import:0603-RES")
      (fields
        (field (name "MANUFACTURER") "Panasonic Electronic Components")
        (field (name "MPN") "ERJ-PB3D3301V")
        (field (name "POWER") "0.3W")
        (field (name "RESISTANCE") "3.3k")
      )
      (libsource (lib "eagle-import") (part "RESISTOR_?_06033.3K"))
    )
    (comp (ref "R92")
      (value "RESISTOR_0603_3.3K")
      (footprint "eagle-import:0603-RES")
      (fields
        (field (name "MANUFACTURER") "Panasonic Electronic Components")
        (field (name "MPN") "ERJ-PB3D3301V")
        (field (name "POWER") "0.3W")
        (field (name "RESISTANCE") "3.3k")
      )
      (libsource (lib "eagle-import") (part "RESISTOR_?_06033.3K"))
    )
    (comp (ref "R93")
      (value "RESISTOR_0603_3.3K")
      (footprint "eagle-import:0603-RES")
      (fields
        (field (name "MANUFACTURER") "Panasonic Electronic Components")
        (field (name "MPN") "ERJ-PB3D3301V")
        (field (name "POWER") "0.3W")
        (field (name "RESISTANCE") "3.3k")
      )
      (libsource (lib "eagle-import") (part "RESISTOR_?_06033.3K"))
    )
    (comp (ref "R94")
      (value "RESISTOR_0603_3.3K")
      (footprint "eagle-import:0603-RES")
      (fields
        (field (name "MANUFACTURER") "Panasonic Electronic Components")
        (field (name "MPN") "ERJ-PB3D3301V")
        (field (name "POWER") "0.3W")
        (field (name "RESISTANCE") "3.3k")
      )
      (libsource (lib "eagle-import") (part "RESISTOR_?_06033.3K"))
    )
    (comp (ref "R95")
      (value "RESISTOR_0603_3.3K")
      (footprint "eagle-import:0603-RES")
      (fields
        (field (name "MANUFACTURER") "Panasonic Electronic Components")
        (field (name "MPN") "ERJ-PB3D3301V")
        (field (name "POWER") "0.3W")
        (field (name "RESISTANCE") "3.3k")
      )
      (libsource (lib "eagle-import") (part "RESISTOR_?_06033.3K"))
    )
    (comp (ref "R96")
      (value "RESISTOR_0603_3.3K")
      (footprint "eagle-import:0603-RES")
      (fields
        (field (name "MANUFACTURER") "Panasonic Electronic Components")
        (field (name "MPN") "ERJ-PB3D3301V")
        (field (name "POWER") "0.3W")
        (field (name "RESISTANCE") "3.3k")
      )
      (libsource (lib "eagle-import") (part "RESISTOR_?_06033.3K"))
    )
    (comp (ref "XF1")
      (value "FUSE_HOLDER_MINIBLADEPTH")
      (footprint "eagle-import:3568")
      (fields (field (name "MANUFACTURER") "Keystone") (field (name "MPN") "3568"))
      (libsource (lib "eagle-import") (part "FUSE_HOLDER_PTHMINIBLADE"))
    )
    (comp (ref "A1")
      (value "TEENSY_4.1")
      (footprint "eagle-import:TEENSY_LONG_EXT")
      (libsource (lib "eagle-import") (part "TEENSY_4.1"))
    )
    (comp (ref "C1")
      (value "CAPACITOR_0603_10V_1UF")
      (footprint "eagle-import:0603-CAP")
      (fields
        (field (name "CAPACITANCE") "1µF")
        (field (name "MANUFACTURER") "Yageo")
        (field (name "MPN") "CC0603KRX7R6BB105")
        (field (name "TOLERANCE") "10%")
        (field (name "VOLTAGE") "10V")
      )
      (libsource (lib "eagle-import") (part "CAPACITOR_?_060310V_1UF"))
    )
    (comp (ref "C2")
      (value "CAPACITOR_0603_10V_1UF")
      (footprint "eagle-import:0603-CAP")
      (fields
        (field (name "CAPACITANCE") "1µF")
        (field (name "MANUFACTURER") "Yageo")
        (field (name "MPN") "CC0603KRX7R6BB105")
        (field (name "TOLERANCE") "10%")
        (field (name "VOLTAGE") "10V")
      )
      (libsource (lib "eagle-import") (part "CAPACITOR_?_060310V_1UF"))
    )
    (comp (ref "C3")
      (value "CAPACITOR_0603_10V_1UF")
      (footprint "eagle-import:0603-CAP")
      (fields
        (field (name "CAPACITANCE") "1µF")
        (field (name "MANUFACTURER") "Yageo")
        (field (name "MPN") "CC0603KRX7R6BB105")
        (field (name "TOLERANCE") "10%")
        (field (name "VOLTAGE") "10V")
      )
      (libsource (lib "eagle-import") (part "CAPACITOR_?_060310V_1UF"))
    )
    (comp (ref "C4")
      (value "CAPACITOR_0603_10V_1UF")
      (footprint "eagle-import:0603-CAP")
      (fields
        (field (name "CAPACITANCE") "1µF")
        (field (name "MANUFACTURER") "Yageo")
        (field (name "MPN") "CC0603KRX7R6BB105")
        (field (name "TOLERANCE") "10%")
        (field (name "VOLTAGE") "10V")
      )
      (libsource (lib "eagle-import") (part "CAPACITOR_?_060310V_1UF"))
    )
    (comp (ref "C5")
      (value "CAPACITOR_0603_10V_1UF")
      (footprint "eagle-import:0603-CAP")
      (fields
        (field (name "CAPACITANCE") "1µF")
        (field (name "MANUFACTURER") "Yageo")
        (field (name "MPN") "CC0603KRX7R6BB105")
        (field (name "TOLERANCE") "10%")
        (field (name "VOLTAGE") "10V")
      )
      (libsource (lib "eagle-import") (part "CAPACITOR_?_060310V_1UF"))
    )
    (comp (ref "C6")
      (value "CAPACITOR_0603_10V_1UF")
      (footprint "eagle-import:0603-CAP")
      (fields
        (field (name "CAPACITANCE") "1µF")
        (field (name "MANUFACTURER") "Yageo")
        (field (name "MPN") "CC0603KRX7R6BB105")
        (field (name "TOLERANCE") "10%")
        (field (name "VOLTAGE") "10V")
      )
      (libsource (lib "eagle-import") (part "CAPACITOR_?_060310V_1UF"))
    )
    (comp (ref "C7")
      (value "CAPACITOR_0603_10V_1UF")
      (footprint "eagle-import:0603-CAP")
      (fields
        (field (name "CAPACITANCE") "1µF")
        (field (name "MANUFACTURER") "Yageo")
        (field (name "MPN") "CC0603KRX7R6BB105")
        (field (name "TOLERANCE") "10%")
        (field (name "VOLTAGE") "10V")
      )
      (libsource (lib "eagle-import") (part "CAPACITOR_?_060310V_1UF"))
    )
    (comp (ref "U$1")
      (value "ADG707")
      (footprint "eagle-import:TSSOP-28")
      (fields (field (name "MPN") "ADG707BRUZ-REEL7") (field (name "MANUFACTURER") "Analog Devices Inc."))
      (libsource (lib "eagle-import") (part "ADG707"))
    )
    (comp (ref "U$2")
      (value "ADG707")
      (footprint "eagle-import:TSSOP-28")
      (fields (field (name "MPN") "ADG707BRUZ-REEL7") (field (name "MANUFACTURER") "Analog Devices Inc."))
      (libsource (lib "eagle-import") (part "ADG707"))
    )
    (comp (ref "U$3")
      (value "ADG707")
      (footprint "eagle-import:TSSOP-28")
      (fields (field (name "MPN") "ADG707BRUZ-REEL7") (field (name "MANUFACTURER") "Analog Devices Inc."))
      (libsource (lib "eagle-import") (part "ADG707"))
    )
    (comp (ref "U$4")
      (value "ADG707")
      (footprint "eagle-import:TSSOP-28")
      (fields (field (name "MPN") "ADG707BRUZ-REEL7") (field (name "MANUFACTURER") "Analog Devices Inc."))
      (libsource (lib "eagle-import") (part "ADG707"))
    )
    (comp (ref "U$5")
      (value "ADG707")
      (footprint "eagle-import:TSSOP-28")
      (fields (field (name "MPN") "ADG707BRUZ-REEL7") (field (name "MANUFACTURER") "Analog Devices Inc."))
      (libsource (lib "eagle-import") (part "ADG707"))
    )
    (comp (ref "U$6")
      (value "ADG707")
      (footprint "eagle-import:TSSOP-28")
      (fields (field (name "MPN") "ADG707BRUZ-REEL7") (field (name "MANUFACTURER") "Analog Devices Inc."))
      (libsource (lib "eagle-import") (part "ADG707"))
    )
  )
  (nets
    (net (code "1") (name "+3V3") (class "Default")
      (node (ref "A1") (pin "3V3") (pinfunction "3.3V_3V3") (pintype "power_in"))
      (node (ref "A1") (pin "3V3@2") (pinfunction "3.3V_3V3@2") (pintype "power_in"))
      (node (ref "A1") (pin "3V3@3") (pinfunction "3.3V_3V3@3") (pintype "power_in"))
      (node (ref "R1") (pin "1") (pinfunction "1_1") (pintype "passive"))
      (node (ref "R10") (pin "1") (pinfunction "1_1") (pintype "passive"))
      (node (ref "R11") (pin "1") (pinfunction "1_1") (pintype "passive"))
      (node (ref "R12") (pin "1") (pinfunction "1_1") (pintype "passive"))
      (node (ref "R13") (pin "1") (pinfunction "1_1") (pintype "passive"))
      (node (ref "R14") (pin "1") (pinfunction "1_1") (pintype "passive"))
      (node (ref "R15") (pin "1") (pinfunction "1_1") (pintype "passive"))
      (node (ref "R16") (pin "1") (pinfunction "1_1") (pintype "passive"))
      (node (ref "R17") (pin "1") (pinfunction "1_1") (pintype "passive"))
      (node (ref "R18") (pin "1") (pinfunction "1_1") (pintype "passive"))
      (node (ref "R19") (pin "1") (pinfunction "1_1") (pintype "passive"))
      (node (ref "R2") (pin "1") (pinfunction "1_1") (pintype "passive"))
      (node (ref "R20") (pin "1") (pinfunction "1_1") (pintype "passive"))
      (node (ref "R21") (pin "1") (pinfunction "1_1") (pintype "passive"))
      (node (ref "R22") (pin "1") (pinfunction "1_1") (pintype "passive"))
      (node (ref "R23") (pin "1") (pinfunction "1_1") (pintype "passive"))
      (node (ref "R24") (pin "1") (pinfunction "1_1") (pintype "passive"))
      (node (ref "R25") (pin "1") (pinfunction "1_1") (pintype "passive"))
      (node (ref "R26") (pin "1") (pinfunction "1_1") (pintype "passive"))
      (node (ref "R27") (pin "1") (pinfunction "1_1") (pintype "passive"))
      (node (ref "R28") (pin "1") (pinfunction "1_1") (pintype "passive"))
      (node (ref "R29") (pin "1") (pinfunction "1_1") (pintype "passive"))
      (node (ref "R3") (pin "1") (pinfunction "1_1") (pintype "passive"))
      (node (ref "R30") (pin "1") (pinfunction "1_1") (pintype "passive"))
      (node (ref "R31") (pin "1") (pinfunction "1_1") (pintype "passive"))
      (node (ref "R32") (pin "1") (pinfunction "1_1") (pintype "passive"))
      (node (ref "R33") (pin "1") (pinfunction "1_1") (pintype "passive"))
      (node (ref "R34") (pin "1") (pinfunction "1_1") (pintype "passive"))
      (node (ref "R35") (pin "1") (pinfunction "1_1") (pintype "passive"))
      (node (ref "R36") (pin "1") (pinfunction "1_1") (pintype "passive"))
      (node (ref "R37") (pin "1") (pinfunction "1_1") (pintype "passive"))
      (node (ref "R38") (pin "1") (pinfunction "1_1") (pintype "passive"))
      (node (ref "R39") (pin "1") (pinfunction "1_1") (pintype "passive"))
      (node (ref "R4") (pin "1") (pinfunction "1_1") (pintype "passive"))
      (node (ref "R40") (pin "1") (pinfunction "1_1") (pintype "passive"))
      (node (ref "R41") (pin "1") (pinfunction "1_1") (pintype "passive"))
      (node (ref "R42") (pin "1") (pinfunction "1_1") (pintype "passive"))
      (node (ref "R43") (pin "1") (pinfunction "1_1") (pintype "passive"))
      (node (ref "R44") (pin "1") (pinfunction "1_1") (pintype "passive"))
      (node (ref "R45") (pin "1") (pinfunction "1_1") (pintype "passive"))
      (node (ref "R46") (pin "1") (pinfunction "1_1") (pintype "passive"))
      (node (ref "R47") (pin "1") (pinfunction "1_1") (pintype "passive"))
      (node (ref "R48") (pin "1") (pinfunction "1_1") (pintype "passive"))
      (node (ref "R49") (pin "1") (pinfunction "1_1") (pintype "passive"))
      (node (ref "R5") (pin "1") (pinfunction "1_1") (pintype "passive"))
      (node (ref "R50") (pin "1") (pinfunction "1_1") (pintype "passive"))
      (node (ref "R51") (pin "1") (pinfunction "1_1") (pintype "passive"))
      (node (ref "R52") (pin "1") (pinfunction "1_1") (pintype "passive"))
      (node (ref "R53") (pin "1") (pinfunction "1_1") (pintype "passive"))
      (node (ref "R54") (pin "1") (pinfunction "1_1") (pintype "passive"))
      (node (ref "R55") (pin "1") (pinfunction "1_1") (pintype "passive"))
      (node (ref "R56") (pin "1") (pinfunction "1_1") (pintype "passive"))
      (node (ref "R57") (pin "1") (pinfunction "1_1") (pintype "passive"))
      (node (ref "R58") (pin "1") (pinfunction "1_1") (pintype "passive"))
      (node (ref "R59") (pin "1") (pinfunction "1_1") (pintype "passive"))
      (node (ref "R6") (pin "1") (pinfunction "1_1") (pintype "passive"))
      (node (ref "R60") (pin "1") (pinfunction "1_1") (pintype "passive"))
      (node (ref "R61") (pin "1") (pinfunction "1_1") (pintype "passive"))
      (node (ref "R62") (pin "1") (pinfunction "1_1") (pintype "passive"))
      (node (ref "R63") (pin "1") (pinfunction "1_1") (pintype "passive"))
      (node (ref "R64") (pin "1") (pinfunction "1_1") (pintype "passive"))
      (node (ref "R65") (pin "1") (pinfunction "1_1") (pintype "passive"))
      (node (ref "R66") (pin "1") (pinfunction "1_1") (pintype "passive"))
      (node (ref "R67") (pin "1") (pinfunction "1_1") (pintype "passive"))
      (node (ref "R68") (pin "1") (pinfunction "1_1") (pintype "passive"))
      (node (ref "R69") (pin "1") (pinfunction "1_1") (pintype "passive"))
      (node (ref "R7") (pin "1") (pinfunction "1_1") (pintype "passive"))
      (node (ref "R70") (pin "1") (pinfunction "1_1") (pintype "passive"))
      (node (ref "R71") (pin "1") (pinfunction "1_1") (pintype "passive"))
      (node (ref "R72") (pin "1") (pinfunction "1_1") (pintype "passive"))
      (node (ref "R73") (pin "1") (pinfunction "1_1") (pintype "passive"))
      (node (ref "R74") (pin "1") (pinfunction "1_1") (pintype "passive"))
      (node (ref "R75") (pin "1") (pinfunction "1_1") (pintype "passive"))
      (node (ref "R76") (pin "1") (pinfunction "1_1") (pintype "passive"))
      (node (ref "R77") (pin "1") (pinfunction "1_1") (pintype "passive"))
      (node (ref "R78") (pin "1") (pinfunction "1_1") (pintype "passive"))
      (node (ref "R79") (pin "1") (pinfunction "1_1") (pintype "passive"))
      (node (ref "R8") (pin "1") (pinfunction "1_1") (pintype "passive"))
      (node (ref "R80") (pin "1") (pinfunction "1_1") (pintype "passive"))
      (node (ref "R81") (pin "1") (pinfunction "1_1") (pintype "passive"))
      (node (ref "R82") (pin "1") (pinfunction "1_1") (pintype "passive"))
      (node (ref "R83") (pin "1") (pinfunction "1_1") (pintype "passive"))
      (node (ref "R84") (pin "1") (pinfunction "1_1") (pintype "passive"))
      (node (ref "R85") (pin "1") (pinfunction "1_1") (pintype "passive"))
      (node (ref "R86") (pin "1") (pinfunction "1_1") (pintype "passive"))
      (node (ref "R87") (pin "1") (pinfunction "1_1") (pintype "passive"))
      (node (ref "R88") (pin "1") (pinfunction "1_1") (pintype "passive"))
      (node (ref "R89") (pin "1") (pinfunction "1_1") (pintype "passive"))
      (node (ref "R9") (pin "1") (pinfunction "1_1") (pintype "passive"))
      (node (ref "R90") (pin "1") (pinfunction "1_1") (pintype "passive"))
      (node (ref "R91") (pin "1") (pinfunction "1_1") (pintype "passive"))
      (node (ref "R92") (pin "1") (pinfunction "1_1") (pintype "passive"))
      (node (ref "R93") (pin "1") (pinfunction "1_1") (pintype "passive"))
      (node (ref "R94") (pin "1") (pinfunction "1_1") (pintype "passive"))
      (node (ref "R95") (pin "1") (pinfunction "1_1") (pintype "passive"))
      (node (ref "R96") (pin "1") (pinfunction "1_1") (pintype "passive"))
    )
    (net (code "2") (name "+5V") (class "Default")
      (node (ref "A1") (pin "VIN") (pinfunction "VIN_VIN") (pintype "power_in"))
      (node (ref "C1") (pin "1") (pinfunction "1_1") (pintype "passive"))
      (node (ref "C2") (pin "1") (pinfunction "1_1") (pintype "passive"))
      (node (ref "C3") (pin "1") (pinfunction "1_1") (pintype "passive"))
      (node (ref "C4") (pin "1") (pinfunction "1_1") (pintype "passive"))
      (node (ref "C5") (pin "1") (pinfunction "1_1") (pintype "passive"))
      (node (ref "C6") (pin "1") (pinfunction "1_1") (pintype "passive"))
      (node (ref "C7") (pin "2") (pinfunction "2_2") (pintype "passive"))
      (node (ref "U$1") (pin "1") (pinfunction "VDD_1") (pintype "power_in"))
      (node (ref "U$1") (pin "18") (pinfunction "EN_18") (pintype "input"))
      (node (ref "U$2") (pin "1") (pinfunction "VDD_1") (pintype "power_in"))
      (node (ref "U$2") (pin "18") (pinfunction "EN_18") (pintype "input"))
      (node (ref "U$3") (pin "1") (pinfunction "VDD_1") (pintype "power_in"))
      (node (ref "U$3") (pin "18") (pinfunction "EN_18") (pintype "input"))
      (node (ref "U$4") (pin "1") (pinfunction "VDD_1") (pintype "power_in"))
      (node (ref "U$4") (pin "18") (pinfunction "EN_18") (pintype "input"))
      (node (ref "U$5") (pin "1") (pinfunction "VDD_1") (pintype "power_in"))
      (node (ref "U$5") (pin "18") (pinfunction "EN_18") (pintype "input"))
      (node (ref "U$6") (pin "1") (pinfunction "VDD_1") (pintype "power_in"))
      (node (ref "U$6") (pin "18") (pinfunction "EN_18") (pintype "input"))
      (node (ref "XF1") (pin "3") (pinfunction "2_3") (pintype "passive"))
      (node (ref "XF1") (pin "4") (pinfunction "2_4") (pintype "passive"))
    )
    (net (code "3") (name "A0") (class "Default")
      (node (ref "A1") (pin "D18") (pinfunction "A4_D18") (pintype "bidirectional"))
      (node (ref "U$2") (pin "28") (pinfunction "DA_28") (pintype "output"))
    )
    (net (code "4") (name "A1") (class "Default")
      (node (ref "A1") (pin "D19") (pinfunction "A5_D19") (pintype "bidirectional"))
      (node (ref "U$2") (pin "2") (pinfunction "DB_2") (pintype "output"))
    )
    (net (code "5") (name "A2") (class "Default")
      (node (ref "A1") (pin "D16") (pinfunction "A2_D16") (pintype "bidirectional"))
      (node (ref "U$1") (pin "28") (pinfunction "DA_28") (pintype "output"))
    )
    (net (code "6") (name "A3") (class "Default")
      (node (ref "A1") (pin "D17") (pinfunction "A3_D17") (pintype "bidirectional"))
      (node (ref "U$1") (pin "2") (pinfunction "DB_2") (pintype "output"))
    )
    (net (code "7") (name "A4") (class "Default")
      (node (ref "A1") (pin "D20") (pinfunction "A6_D20") (pintype "bidirectional"))
      (node (ref "U$4") (pin "28") (pinfunction "DA_28") (pintype "output"))
    )
    (net (code "8") (name "A5") (class "Default")
      (node (ref "A1") (pin "D21") (pinfunction "A7_D21") (pintype "bidirectional"))
      (node (ref "U$4") (pin "2") (pinfunction "DB_2") (pintype "output"))
    )
    (net (code "9") (name "A6") (class "Default")
      (node (ref "A1") (pin "D14") (pinfunction "A0_D14") (pintype "bidirectional"))
      (node (ref "U$3") (pin "28") (pinfunction "DA_28") (pintype "output"))
    )
    (net (code "10") (name "A7") (class "Default")
      (node (ref "A1") (pin "D15") (pinfunction "A1_D15") (pintype "bidirectional"))
      (node (ref "U$3") (pin "2") (pinfunction "DB_2") (pintype "output"))
    )
    (net (code "11") (name "A8") (class "Default")
      (node (ref "A1") (pin "D22") (pinfunction "A8_D22") (pintype "bidirectional"))
      (node (ref "U$6") (pin "28") (pinfunction "DA_28") (pintype "output"))
    )
    (net (code "12") (name "A9") (class "Default")
      (node (ref "A1") (pin "D23") (pinfunction "A9_D23") (pintype "bidirectional"))
      (node (ref "U$6") (pin "2") (pinfunction "DB_2") (pintype "output"))
    )
    (net (code "13") (name "A10") (class "Default")
      (node (ref "A1") (pin "D24") (pinfunction "A10_D24") (pintype "bidirectional"))
      (node (ref "U$5") (pin "28") (pinfunction "DA_28") (pintype "output"))
    )
    (net (code "14") (name "A11") (class "Default")
      (node (ref "A1") (pin "D25") (pinfunction "A11_D25") (pintype "bidirectional"))
      (node (ref "U$5") (pin "2") (pinfunction "DB_2") (pintype "output"))
    )
    (net (code "15") (name "D0") (class "Default")
      (node (ref "J7") (pin "1") (pinfunction "1_1") (pintype "passive"))
      (node (ref "R49") (pin "2") (pinfunction "2_2") (pintype "passive"))
      (node (ref "U$2") (pin "19") (pinfunction "S1A_19") (pintype "input"))
    )
    (net (code "16") (name "D1") (class "Default")
      (node (ref "J7") (pin "2") (pinfunction "2_2") (pintype "passive"))
      (node (ref "R58") (pin "2") (pinfunction "2_2") (pintype "passive"))
      (node (ref "U$2") (pin "20") (pinfunction "S2A_20") (pintype "input"))
    )
    (net (code "17") (name "D2") (class "Default")
      (node (ref "J7") (pin "3") (pinfunction "3_3") (pintype "passive"))
      (node (ref "R59") (pin "2") (pinfunction "2_2") (pintype "passive"))
      (node (ref "U$2") (pin "21") (pinfunction "S3A_21") (pintype "input"))
    )
    (net (code "18") (name "D3") (class "Default")
      (node (ref "J7") (pin "4") (pinfunction "4_4") (pintype "passive"))
      (node (ref "R60") (pin "2") (pinfunction "2_2") (pintype "passive"))
      (node (ref "U$2") (pin "22") (pinfunction "S4A_22") (pintype "input"))
    )
    (net (code "19") (name "D4") (class "Default")
      (node (ref "J7") (pin "5") (pinfunction "5_5") (pintype "passive"))
      (node (ref "R61") (pin "2") (pinfunction "2_2") (pintype "passive"))
      (node (ref "U$2") (pin "23") (pinfunction "S5A_23") (pintype "input"))
    )
    (net (code "20") (name "D5") (class "Default")
      (node (ref "J7") (pin "6") (pinfunction "6_6") (pintype "passive"))
      (node (ref "R62") (pin "2") (pinfunction "2_2") (pintype "passive"))
      (node (ref "U$2") (pin "24") (pinfunction "S6A_24") (pintype "input"))
    )
    (net (code "21") (name "D6") (class "Default")
      (node (ref "J7") (pin "7") (pinfunction "7_7") (pintype "passive"))
      (node (ref "R63") (pin "2") (pinfunction "2_2") (pintype "passive"))
      (node (ref "U$2") (pin "25") (pinfunction "S7A_25") (pintype "input"))
    )
    (net (code "22") (name "D7") (class "Default")
      (node (ref "J7") (pin "8") (pinfunction "8_8") (pintype "passive"))
      (node (ref "R64") (pin "2") (pinfunction "2_2") (pintype "passive"))
      (node (ref "U$2") (pin "26") (pinfunction "S8A_26") (pintype "input"))
    )
    (net (code "23") (name "D8") (class "Default")
      (node (ref "J8") (pin "1") (pinfunction "1_1") (pintype "passive"))
      (node (ref "R65") (pin "2") (pinfunction "2_2") (pintype "passive"))
      (node (ref "U$2") (pin "11") (pinfunction "S1B_11") (pintype "input"))
    )
    (net (code "24") (name "D9") (class "Default")
      (node (ref "J8") (pin "2") (pinfunction "2_2") (pintype "passive"))
      (node (ref "R66") (pin "2") (pinfunction "2_2") (pintype "passive"))
      (node (ref "U$2") (pin "10") (pinfunction "S2B_10") (pintype "input"))
    )
    (net (code "25") (name "D10") (class "Default")
      (node (ref "J8") (pin "3") (pinfunction "3_3") (pintype "passive"))
      (node (ref "R50") (pin "2") (pinfunction "2_2") (pintype "passive"))
      (node (ref "U$2") (pin "9") (pinfunction "S3B_9") (pintype "input"))
    )
    (net (code "26") (name "D11") (class "Default")
      (node (ref "J8") (pin "4") (pinfunction "4_4") (pintype "passive"))
      (node (ref "R51") (pin "2") (pinfunction "2_2") (pintype "passive"))
      (node (ref "U$2") (pin "8") (pinfunction "S4B_8") (pintype "input"))
    )
    (net (code "27") (name "D12") (class "Default")
      (node (ref "J8") (pin "5") (pinfunction "5_5") (pintype "passive"))
      (node (ref "R52") (pin "2") (pinfunction "2_2") (pintype "passive"))
      (node (ref "U$2") (pin "7") (pinfunction "S5B_7") (pintype "input"))
    )
    (net (code "28") (name "D13") (class "Default")
      (node (ref "J8") (pin "6") (pinfunction "6_6") (pintype "passive"))
      (node (ref "R53") (pin "2") (pinfunction "2_2") (pintype "passive"))
      (node (ref "U$2") (pin "6") (pinfunction "S6B_6") (pintype "input"))
    )
    (net (code "29") (name "D14") (class "Default")
      (node (ref "J8") (pin "7") (pinfunction "7_7") (pintype "passive"))
      (node (ref "R54") (pin "2") (pinfunction "2_2") (pintype "passive"))
      (node (ref "U$2") (pin "5") (pinfunction "S7B_5") (pintype "input"))
    )
    (net (code "30") (name "D15") (class "Default")
      (node (ref "J8") (pin "8") (pinfunction "8_8") (pintype "passive"))
      (node (ref "R55") (pin "2") (pinfunction "2_2") (pintype "passive"))
      (node (ref "U$2") (pin "4") (pinfunction "S8B_4") (pintype "input"))
    )
    (net (code "31") (name "D16") (class "Default")
      (node (ref "J9") (pin "1") (pinfunction "1_1") (pintype "passive"))
      (node (ref "R56") (pin "2") (pinfunction "2_2") (pintype "passive"))
      (node (ref "U$1") (pin "19") (pinfunction "S1A_19") (pintype "input"))
    )
    (net (code "32") (name "D17") (class "Default")
      (node (ref "J9") (pin "2") (pinfunction "2_2") (pintype "passive"))
      (node (ref "R57") (pin "2") (pinfunction "2_2") (pintype "passive"))
      (node (ref "U$1") (pin "20") (pinfunction "S2A_20") (pintype "input"))
    )
    (net (code "33") (name "D18") (class "Default")
      (node (ref "J9") (pin "3") (pinfunction "3_3") (pintype "passive"))
      (node (ref "R67") (pin "2") (pinfunction "2_2") (pintype "passive"))
      (node (ref "U$1") (pin "21") (pinfunction "S3A_21") (pintype "input"))
    )
    (net (code "34") (name "D19") (class "Default")
      (node (ref "J9") (pin "4") (pinfunction "4_4") (pintype "passive"))
      (node (ref "R76") (pin "2") (pinfunction "2_2") (pintype "passive"))
      (node (ref "U$1") (pin "22") (pinfunction "S4A_22") (pintype "input"))
    )
    (net (code "35") (name "D20") (class "Default")
      (node (ref "J9") (pin "5") (pinfunction "5_5") (pintype "passive"))
      (node (ref "R77") (pin "2") (pinfunction "2_2") (pintype "passive"))
      (node (ref "U$1") (pin "23") (pinfunction "S5A_23") (pintype "input"))
    )
    (net (code "36") (name "D21") (class "Default")
      (node (ref "J9") (pin "6") (pinfunction "6_6") (pintype "passive"))
      (node (ref "R78") (pin "2") (pinfunction "2_2") (pintype "passive"))
      (node (ref "U$1") (pin "24") (pinfunction "S6A_24") (pintype "input"))
    )
    (net (code "37") (name "D22") (class "Default")
      (node (ref "J9") (pin "7") (pinfunction "7_7") (pintype "passive"))
      (node (ref "R79") (pin "2") (pinfunction "2_2") (pintype "passive"))
      (node (ref "U$1") (pin "25") (pinfunction "S7A_25") (pintype "input"))
    )
    (net (code "38") (name "D23") (class "Default")
      (node (ref "J9") (pin "8") (pinfunction "8_8") (pintype "passive"))
      (node (ref "R80") (pin "2") (pinfunction "2_2") (pintype "passive"))
      (node (ref "U$1") (pin "26") (pinfunction "S8A_26") (pintype "input"))
    )
    (net (code "39") (name "D24") (class "Default")
      (node (ref "J10") (pin "1") (pinfunction "1_1") (pintype "passive"))
      (node (ref "R81") (pin "2") (pinfunction "2_2") (pintype "passive"))
      (node (ref "U$1") (pin "11") (pinfunction "S1B_11") (pintype "input"))
    )
    (net (code "40") (name "D25") (class "Default")
      (node (ref "J10") (pin "2") (pinfunction "2_2") (pintype "passive"))
      (node (ref "R82") (pin "2") (pinfunction "2_2") (pintype "passive"))
      (node (ref "U$1") (pin "10") (pinfunction "S2B_10") (pintype "input"))
    )
    (net (code "41") (name "D26") (class "Default")
      (node (ref "J10") (pin "3") (pinfunction "3_3") (pintype "passive"))
      (node (ref "R83") (pin "2") (pinfunction "2_2") (pintype "passive"))
      (node (ref "U$1") (pin "9") (pinfunction "S3B_9") (pintype "input"))
    )
    (net (code "42") (name "D27") (class "Default")
      (node (ref "J10") (pin "4") (pinfunction "4_4") (pintype "passive"))
      (node (ref "R84") (pin "2") (pinfunction "2_2") (pintype "passive"))
      (node (ref "U$1") (pin "8") (pinfunction "S4B_8") (pintype "input"))
    )
    (net (code "43") (name "D28") (class "Default")
      (node (ref "J10") (pin "5") (pinfunction "5_5") (pintype "passive"))
      (node (ref "R68") (pin "2") (pinfunction "2_2") (pintype "passive"))
      (node (ref "U$1") (pin "7") (pinfunction "S5B_7") (pintype "input"))
    )
    (net (code "44") (name "D29") (class "Default")
      (node (ref "J10") (pin "6") (pinfunction "6_6") (pintype "passive"))
      (node (ref "R69") (pin "2") (pinfunction "2_2") (pintype "passive"))
      (node (ref "U$1") (pin "6") (pinfunction "S6B_6") (pintype "input"))
    )
    (net (code "45") (name "D30") (class "Default")
      (node (ref "J10") (pin "7") (pinfunction "7_7") (pintype "passive"))
      (node (ref "R70") (pin "2") (pinfunction "2_2") (pintype "passive"))
      (node (ref "U$1") (pin "5") (pinfunction "S7B_5") (pintype "input"))
    )
    (net (code "46") (name "D31") (class "Default")
      (node (ref "J10") (pin "8") (pinfunction "8_8") (pintype "passive"))
      (node (ref "R71") (pin "2") (pinfunction "2_2") (pintype "passive"))
      (node (ref "U$1") (pin "4") (pinfunction "S8B_4") (pintype "input"))
    )
    (net (code "47") (name "D32") (class "Default")
      (node (ref "J11") (pin "1") (pinfunction "1_1") (pintype "passive"))
      (node (ref "R72") (pin "2") (pinfunction "2_2") (pintype "passive"))
      (node (ref "U$4") (pin "19") (pinfunction "S1A_19") (pintype "input"))
    )
    (net (code "48") (name "D33") (class "Default")
      (node (ref "J11") (pin "2") (pinfunction "2_2") (pintype "passive"))
      (node (ref "R73") (pin "2") (pinfunction "2_2") (pintype "passive"))
      (node (ref "U$4") (pin "20") (pinfunction "S2A_20") (pintype "input"))
    )
    (net (code "49") (name "D34") (class "Default")
      (node (ref "J11") (pin "3") (pinfunction "3_3") (pintype "passive"))
      (node (ref "R74") (pin "2") (pinfunction "2_2") (pintype "passive"))
      (node (ref "U$4") (pin "21") (pinfunction "S3A_21") (pintype "input"))
    )
    (net (code "50") (name "D35") (class "Default")
      (node (ref "J11") (pin "4") (pinfunction "4_4") (pintype "passive"))
      (node (ref "R75") (pin "2") (pinfunction "2_2") (pintype "passive"))
      (node (ref "U$4") (pin "22") (pinfunction "S4A_22") (pintype "input"))
    )
    (net (code "51") (name "D36") (class "Default")
      (node (ref "J11") (pin "5") (pinfunction "5_5") (pintype "passive"))
      (node (ref "R93") (pin "2") (pinfunction "2_2") (pintype "passive"))
      (node (ref "U$4") (pin "23") (pinfunction "S5A_23") (pintype "input"))
    )
    (net (code "52") (name "D37") (class "Default")
      (node (ref "J11") (pin "6") (pinfunction "6_6") (pintype "passive"))
      (node (ref "R94") (pin "2") (pinfunction "2_2") (pintype "passive"))
      (node (ref "U$4") (pin "24") (pinfunction "S6A_24") (pintype "input"))
    )
    (net (code "53") (name "D38") (class "Default")
      (node (ref "J11") (pin "7") (pinfunction "7_7") (pintype "passive"))
      (node (ref "R95") (pin "2") (pinfunction "2_2") (pintype "passive"))
      (node (ref "U$4") (pin "25") (pinfunction "S7A_25") (pintype "input"))
    )
    (net (code "54") (name "D39") (class "Default")
      (node (ref "J11") (pin "8") (pinfunction "8_8") (pintype "passive"))
      (node (ref "R96") (pin "2") (pinfunction "2_2") (pintype "passive"))
      (node (ref "U$4") (pin "26") (pinfunction "S8A_26") (pintype "input"))
    )
    (net (code "55") (name "D40") (class "Default")
      (node (ref "J12") (pin "1") (pinfunction "1_1") (pintype "passive"))
      (node (ref "R85") (pin "2") (pinfunction "2_2") (pintype "passive"))
      (node (ref "U$4") (pin "11") (pinfunction "S1B_11") (pintype "input"))
    )
    (net (code "56") (name "D41") (class "Default")
      (node (ref "J12") (pin "2") (pinfunction "2_2") (pintype "passive"))
      (node (ref "R86") (pin "2") (pinfunction "2_2") (pintype "passive"))
      (node (ref "U$4") (pin "10") (pinfunction "S2B_10") (pintype "input"))
    )
    (net (code "57") (name "D42") (class "Default")
      (node (ref "J12") (pin "3") (pinfunction "3_3") (pintype "passive"))
      (node (ref "R87") (pin "2") (pinfunction "2_2") (pintype "passive"))
      (node (ref "U$4") (pin "9") (pinfunction "S3B_9") (pintype "input"))
    )
    (net (code "58") (name "D43") (class "Default")
      (node (ref "J12") (pin "4") (pinfunction "4_4") (pintype "passive"))
      (node (ref "R88") (pin "2") (pinfunction "2_2") (pintype "passive"))
      (node (ref "U$4") (pin "8") (pinfunction "S4B_8") (pintype "input"))
    )
    (net (code "59") (name "D44") (class "Default")
      (node (ref "J12") (pin "5") (pinfunction "5_5") (pintype "passive"))
      (node (ref "R89") (pin "2") (pinfunction "2_2") (pintype "passive"))
      (node (ref "U$4") (pin "7") (pinfunction "S5B_7") (pintype "input"))
    )
    (net (code "60") (name "D45") (class "Default")
      (node (ref "J12") (pin "6") (pinfunction "6_6") (pintype "passive"))
      (node (ref "R90") (pin "2") (pinfunction "2_2") (pintype "passive"))
      (node (ref "U$4") (pin "6") (pinfunction "S6B_6") (pintype "input"))
    )
    (net (code "61") (name "D46") (class "Default")
      (node (ref "J12") (pin "7") (pinfunction "7_7") (pintype "passive"))
      (node (ref "R91") (pin "2") (pinfunction "2_2") (pintype "passive"))
      (node (ref "U$4") (pin "5") (pinfunction "S7B_5") (pintype "input"))
    )
    (net (code "62") (name "D47") (class "Default")
      (node (ref "J12") (pin "8") (pinfunction "8_8") (pintype "passive"))
      (node (ref "R92") (pin "2") (pinfunction "2_2") (pintype "passive"))
      (node (ref "U$4") (pin "4") (pinfunction "S8B_4") (pintype "input"))
    )
    (net (code "63") (name "D48") (class "Default")
      (node (ref "J1") (pin "1") (pinfunction "1_1") (pintype "passive"))
      (node (ref "R1") (pin "2") (pinfunction "2_2") (pintype "passive"))
      (node (ref "U$3") (pin "19") (pinfunction "S1A_19") (pintype "input"))
    )
    (net (code "64") (name "D49") (class "Default")
      (node (ref "J1") (pin "2") (pinfunction "2_2") (pintype "passive"))
      (node (ref "R10") (pin "2") (pinfunction "2_2") (pintype "passive"))
      (node (ref "U$3") (pin "20") (pinfunction "S2A_20") (pintype "input"))
    )
    (net (code "65") (name "D50") (class "Default")
      (node (ref "J1") (pin "3") (pinfunction "3_3") (pintype "passive"))
      (node (ref "R11") (pin "2") (pinfunction "2_2") (pintype "passive"))
      (node (ref "U$3") (pin "21") (pinfunction "S3A_21") (pintype "input"))
    )
    (net (code "66") (name "D51") (class "Default")
      (node (ref "J1") (pin "4") (pinfunction "4_4") (pintype "passive"))
      (node (ref "R12") (pin "2") (pinfunction "2_2") (pintype "passive"))
      (node (ref "U$3") (pin "22") (pinfunction "S4A_22") (pintype "input"))
    )
    (net (code "67") (name "D52") (class "Default")
      (node (ref "J1") (pin "5") (pinfunction "5_5") (pintype "passive"))
      (node (ref "R13") (pin "2") (pinfunction "2_2") (pintype "passive"))
      (node (ref "U$3") (pin "23") (pinfunction "S5A_23") (pintype "input"))
    )
    (net (code "68") (name "D53") (class "Default")
      (node (ref "J1") (pin "6") (pinfunction "6_6") (pintype "passive"))
      (node (ref "R14") (pin "2") (pinfunction "2_2") (pintype "passive"))
      (node (ref "U$3") (pin "24") (pinfunction "S6A_24") (pintype "input"))
    )
    (net (code "69") (name "D54") (class "Default")
      (node (ref "J1") (pin "7") (pinfunction "7_7") (pintype "passive"))
      (node (ref "R15") (pin "2") (pinfunction "2_2") (pintype "passive"))
      (node (ref "U$3") (pin "25") (pinfunction "S7A_25") (pintype "input"))
    )
    (net (code "70") (name "D55") (class "Default")
      (node (ref "J1") (pin "8") (pinfunction "8_8") (pintype "passive"))
      (node (ref "R16") (pin "2") (pinfunction "2_2") (pintype "passive"))
      (node (ref "U$3") (pin "26") (pinfunction "S8A_26") (pintype "input"))
    )
    (net (code "71") (name "D56") (class "Default")
      (node (ref "J2") (pin "1") (pinfunction "1_1") (pintype "passive"))
      (node (ref "R17") (pin "2") (pinfunction "2_2") (pintype "passive"))
      (node (ref "U$3") (pin "11") (pinfunction "S1B_11") (pintype "input"))
    )
    (net (code "72") (name "D57") (class "Default")
      (node (ref "J2") (pin "2") (pinfunction "2_2") (pintype "passive"))
      (node (ref "R18") (pin "2") (pinfunction "2_2") (pintype "passive"))
      (node (ref "U$3") (pin "10") (pinfunction "S2B_10") (pintype "input"))
    )
    (net (code "73") (name "D58") (class "Default")
      (node (ref "J2") (pin "3") (pinfunction "3_3") (pintype "passive"))
      (node (ref "R2") (pin "2") (pinfunction "2_2") (pintype "passive"))
      (node (ref "U$3") (pin "9") (pinfunction "S3B_9") (pintype "input"))
    )
    (net (code "74") (name "D59") (class "Default")
      (node (ref "J2") (pin "4") (pinfunction "4_4") (pintype "passive"))
      (node (ref "R3") (pin "2") (pinfunction "2_2") (pintype "passive"))
      (node (ref "U$3") (pin "8") (pinfunction "S4B_8") (pintype "input"))
    )
    (net (code "75") (name "D60") (class "Default")
      (node (ref "J2") (pin "5") (pinfunction "5_5") (pintype "passive"))
      (node (ref "R4") (pin "2") (pinfunction "2_2") (pintype "passive"))
      (node (ref "U$3") (pin "7") (pinfunction "S5B_7") (pintype "input"))
    )
    (net (code "76") (name "D61") (class "Default")
      (node (ref "J2") (pin "6") (pinfunction "6_6") (pintype "passive"))
      (node (ref "R5") (pin "2") (pinfunction "2_2") (pintype "passive"))
      (node (ref "U$3") (pin "6") (pinfunction "S6B_6") (pintype "input"))
    )
    (net (code "77") (name "D62") (class "Default")
      (node (ref "J2") (pin "7") (pinfunction "7_7") (pintype "passive"))
      (node (ref "R6") (pin "2") (pinfunction "2_2") (pintype "passive"))
      (node (ref "U$3") (pin "5") (pinfunction "S7B_5") (pintype "input"))
    )
    (net (code "78") (name "D63") (class "Default")
      (node (ref "J2") (pin "8") (pinfunction "8_8") (pintype "passive"))
      (node (ref "R7") (pin "2") (pinfunction "2_2") (pintype "passive"))
      (node (ref "U$3") (pin "4") (pinfunction "S8B_4") (pintype "input"))
    )
    (net (code "79") (name "D64") (class "Default")
      (node (ref "J3") (pin "1") (pinfunction "1_1") (pintype "passive"))
      (node (ref "R8") (pin "2") (pinfunction "2_2") (pintype "passive"))
      (node (ref "U$6") (pin "19") (pinfunction "S1A_19") (pintype "input"))
    )
    (net (code "80") (name "D65") (class "Default")
      (node (ref "J3") (pin "2") (pinfunction "2_2") (pintype "passive"))
      (node (ref "R9") (pin "2") (pinfunction "2_2") (pintype "passive"))
      (node (ref "U$6") (pin "20") (pinfunction "S2A_20") (pintype "input"))
    )
    (net (code "81") (name "D66") (class "Default")
      (node (ref "J3") (pin "3") (pinfunction "3_3") (pintype "passive"))
      (node (ref "R19") (pin "2") (pinfunction "2_2") (pintype "passive"))
      (node (ref "U$6") (pin "21") (pinfunction "S3A_21") (pintype "input"))
    )
    (net (code "82") (name "D67") (class "Default")
      (node (ref "J3") (pin "4") (pinfunction "4_4") (pintype "passive"))
      (node (ref "R28") (pin "2") (pinfunction "2_2") (pintype "passive"))
      (node (ref "U$6") (pin "22") (pinfunction "S4A_22") (pintype "input"))
    )
    (net (code "83") (name "D68") (class "Default")
      (node (ref "J3") (pin "5") (pinfunction "5_5") (pintype "passive"))
      (node (ref "R29") (pin "2") (pinfunction "2_2") (pintype "passive"))
      (node (ref "U$6") (pin "23") (pinfunction "S5A_23") (pintype "input"))
    )
    (net (code "84") (name "D69") (class "Default")
      (node (ref "J3") (pin "6") (pinfunction "6_6") (pintype "passive"))
      (node (ref "R30") (pin "2") (pinfunction "2_2") (pintype "passive"))
      (node (ref "U$6") (pin "24") (pinfunction "S6A_24") (pintype "input"))
    )
    (net (code "85") (name "D70") (class "Default")
      (node (ref "J3") (pin "7") (pinfunction "7_7") (pintype "passive"))
      (node (ref "R31") (pin "2") (pinfunction "2_2") (pintype "passive"))
      (node (ref "U$6") (pin "25") (pinfunction "S7A_25") (pintype "input"))
    )
    (net (code "86") (name "D71") (class "Default")
      (node (ref "J3") (pin "8") (pinfunction "8_8") (pintype "passive"))
      (node (ref "R32") (pin "2") (pinfunction "2_2") (pintype "passive"))
      (node (ref "U$6") (pin "26") (pinfunction "S8A_26") (pintype "input"))
    )
    (net (code "87") (name "D72") (class "Default")
      (node (ref "J4") (pin "1") (pinfunction "1_1") (pintype "passive"))
      (node (ref "R33") (pin "2") (pinfunction "2_2") (pintype "passive"))
      (node (ref "U$6") (pin "11") (pinfunction "S1B_11") (pintype "input"))
    )
    (net (code "88") (name "D73") (class "Default")
      (node (ref "J4") (pin "2") (pinfunction "2_2") (pintype "passive"))
      (node (ref "R34") (pin "2") (pinfunction "2_2") (pintype "passive"))
      (node (ref "U$6") (pin "10") (pinfunction "S2B_10") (pintype "input"))
    )
    (net (code "89") (name "D74") (class "Default")
      (node (ref "J4") (pin "3") (pinfunction "3_3") (pintype "passive"))
      (node (ref "R35") (pin "2") (pinfunction "2_2") (pintype "passive"))
      (node (ref "U$6") (pin "9") (pinfunction "S3B_9") (pintype "input"))
    )
    (net (code "90") (name "D75") (class "Default")
      (node (ref "J4") (pin "4") (pinfunction "4_4") (pintype "passive"))
      (node (ref "R36") (pin "2") (pinfunction "2_2") (pintype "passive"))
      (node (ref "U$6") (pin "8") (pinfunction "S4B_8") (pintype "input"))
    )
    (net (code "91") (name "D76") (class "Default")
      (node (ref "J4") (pin "5") (pinfunction "5_5") (pintype "passive"))
      (node (ref "R20") (pin "2") (pinfunction "2_2") (pintype "passive"))
      (node (ref "U$6") (pin "7") (pinfunction "S5B_7") (pintype "input"))
    )
    (net (code "92") (name "D77") (class "Default")
      (node (ref "J4") (pin "6") (pinfunction "6_6") (pintype "passive"))
      (node (ref "R21") (pin "2") (pinfunction "2_2") (pintype "passive"))
      (node (ref "U$6") (pin "6") (pinfunction "S6B_6") (pintype "input"))
    )
    (net (code "93") (name "D78") (class "Default")
      (node (ref "J4") (pin "7") (pinfunction "7_7") (pintype "passive"))
      (node (ref "R22") (pin "2") (pinfunction "2_2") (pintype "passive"))
      (node (ref "U$6") (pin "5") (pinfunction "S7B_5") (pintype "input"))
    )
    (net (code "94") (name "D79") (class "Default")
      (node (ref "J4") (pin "8") (pinfunction "8_8") (pintype "passive"))
      (node (ref "R23") (pin "2") (pinfunction "2_2") (pintype "passive"))
      (node (ref "U$6") (pin "4") (pinfunction "S8B_4") (pintype "input"))
    )
    (net (code "95") (name "D80") (class "Default")
      (node (ref "J5") (pin "1") (pinfunction "1_1") (pintype "passive"))
      (node (ref "R24") (pin "2") (pinfunction "2_2") (pintype "passive"))
      (node (ref "U$5") (pin "19") (pinfunction "S1A_19") (pintype "input"))
    )
    (net (code "96") (name "D81") (class "Default")
      (node (ref "J5") (pin "2") (pinfunction "2_2") (pintype "passive"))
      (node (ref "R25") (pin "2") (pinfunction "2_2") (pintype "passive"))
      (node (ref "U$5") (pin "20") (pinfunction "S2A_20") (pintype "input"))
    )
    (net (code "97") (name "D82") (class "Default")
      (node (ref "J5") (pin "3") (pinfunction "3_3") (pintype "passive"))
      (node (ref "R26") (pin "2") (pinfunction "2_2") (pintype "passive"))
      (node (ref "U$5") (pin "21") (pinfunction "S3A_21") (pintype "input"))
    )
    (net (code "98") (name "D83") (class "Default")
      (node (ref "J5") (pin "4") (pinfunction "4_4") (pintype "passive"))
      (node (ref "R27") (pin "2") (pinfunction "2_2") (pintype "passive"))
      (node (ref "U$5") (pin "22") (pinfunction "S4A_22") (pintype "input"))
    )
    (net (code "99") (name "D84") (class "Default")
      (node (ref "J5") (pin "5") (pinfunction "5_5") (pintype "passive"))
      (node (ref "R45") (pin "2") (pinfunction "2_2") (pintype "passive"))
      (node (ref "U$5") (pin "23") (pinfunction "S5A_23") (pintype "input"))
    )
    (net (code "100") (name "D85") (class "Default")
      (node (ref "J5") (pin "6") (pinfunction "6_6") (pintype "passive"))
      (node (ref "R46") (pin "2") (pinfunction "2_2") (pintype "passive"))
      (node (ref "U$5") (pin "24") (pinfunction "S6A_24") (pintype "input"))
    )
    (net (code "101") (name "D86") (class "Default")
      (node (ref "J5") (pin "7") (pinfunction "7_7") (pintype "passive"))
      (node (ref "R47") (pin "2") (pinfunction "2_2") (pintype "passive"))
      (node (ref "U$5") (pin "25") (pinfunction "S7A_25") (pintype "input"))
    )
    (net (code "102") (name "D87") (class "Default")
      (node (ref "J5") (pin "8") (pinfunction "8_8") (pintype "passive"))
      (node (ref "R48") (pin "2") (pinfunction "2_2") (pintype "passive"))
      (node (ref "U$5") (pin "26") (pinfunction "S8A_26") (pintype "input"))
    )
    (net (code "103") (name "D88") (class "Default")
      (node (ref "J6") (pin "1") (pinfunction "1_1") (pintype "passive"))
      (node (ref "R37") (pin "2") (pinfunction "2_2") (pintype "passive"))
      (node (ref "U$5") (pin "11") (pinfunction "S1B_11") (pintype "input"))
    )
    (net (code "104") (name "D89") (class "Default")
      (node (ref "J6") (pin "2") (pinfunction "2_2") (pintype "passive"))
      (node (ref "R38") (pin "2") (pinfunction "2_2") (pintype "passive"))
      (node (ref "U$5") (pin "10") (pinfunction "S2B_10") (pintype "input"))
    )
    (net (code "105") (name "D90") (class "Default")
      (node (ref "J6") (pin "3") (pinfunction "3_3") (pintype "passive"))
      (node (ref "R39") (pin "2") (pinfunction "2_2") (pintype "passive"))
      (node (ref "U$5") (pin "9") (pinfunction "S3B_9") (pintype "input"))
    )
    (net (code "106") (name "D91") (class "Default")
      (node (ref "J6") (pin "4") (pinfunction "4_4") (pintype "passive"))
      (node (ref "R40") (pin "2") (pinfunction "2_2") (pintype "passive"))
      (node (ref "U$5") (pin "8") (pinfunction "S4B_8") (pintype "input"))
    )
    (net (code "107") (name "D92") (class "Default")
      (node (ref "J6") (pin "5") (pinfunction "5_5") (pintype "passive"))
      (node (ref "R41") (pin "2") (pinfunction "2_2") (pintype "passive"))
      (node (ref "U$5") (pin "7") (pinfunction "S5B_7") (pintype "input"))
    )
    (net (code "108") (name "D93") (class "Default")
      (node (ref "J6") (pin "6") (pinfunction "6_6") (pintype "passive"))
      (node (ref "R42") (pin "2") (pinfunction "2_2") (pintype "passive"))
      (node (ref "U$5") (pin "6") (pinfunction "S6B_6") (pintype "input"))
    )
    (net (code "109") (name "D94") (class "Default")
      (node (ref "J6") (pin "7") (pinfunction "7_7") (pintype "passive"))
      (node (ref "R43") (pin "2") (pinfunction "2_2") (pintype "passive"))
      (node (ref "U$5") (pin "5") (pinfunction "S7B_5") (pintype "input"))
    )
    (net (code "110") (name "D95") (class "Default")
      (node (ref "J6") (pin "8") (pinfunction "8_8") (pintype "passive"))
      (node (ref "R44") (pin "2") (pinfunction "2_2") (pintype "passive"))
      (node (ref "U$5") (pin "4") (pinfunction "S8B_4") (pintype "input"))
    )
    (net (code "111") (name "GND") (class "Default")
      (node (ref "A1") (pin "AGND/GND") (pinfunction "GND_AGND/GND") (pintype "bidirectional"))
      (node (ref "A1") (pin "GND") (pinfunction "GND_GND") (pintype "bidirectional"))
      (node (ref "A1") (pin "GND@2") (pinfunction "GND_GND@2") (pintype "bidirectional"))
      (node (ref "C1") (pin "2") (pinfunction "2_2") (pintype "passive"))
      (node (ref "C2") (pin "2") (pinfunction "2_2") (pintype "passive"))
      (node (ref "C3") (pin "2") (pinfunction "2_2") (pintype "passive"))
      (node (ref "C4") (pin "2") (pinfunction "2_2") (pintype "passive"))
      (node (ref "C5") (pin "2") (pinfunction "2_2") (pintype "passive"))
      (node (ref "C6") (pin "2") (pinfunction "2_2") (pintype "passive"))
      (node (ref "C7") (pin "1") (pinfunction "1_1") (pintype "passive"))
      (node (ref "D2") (pin "A") (pinfunction "A_A") (pintype "passive"))
      (node (ref "J1") (pin "10") (pinfunction "10_10") (pintype "passive"))
      (node (ref "J1") (pin "11") (pinfunction "11_11") (pintype "passive"))
      (node (ref "J1") (pin "12") (pinfunction "12_12") (pintype "passive"))
      (node (ref "J1") (pin "13") (pinfunction "13_13") (pintype "passive"))
      (node (ref "J1") (pin "14") (pinfunction "14_14") (pintype "passive"))
      (node (ref "J1") (pin "15") (pinfunction "15_15") (pintype "passive"))
      (node (ref "J1") (pin "16") (pinfunction "16_16") (pintype "passive"))
      (node (ref "J1") (pin "9") (pinfunction "9_9") (pintype "passive"))
      (node (ref "J10") (pin "10") (pinfunction "10_10") (pintype "passive"))
      (node (ref "J10") (pin "11") (pinfunction "11_11") (pintype "passive"))
      (node (ref "J10") (pin "12") (pinfunction "12_12") (pintype "passive"))
      (node (ref "J10") (pin "13") (pinfunction "13_13") (pintype "passive"))
      (node (ref "J10") (pin "14") (pinfunction "14_14") (pintype "passive"))
      (node (ref "J10") (pin "15") (pinfunction "15_15") (pintype "passive"))
      (node (ref "J10") (pin "16") (pinfunction "16_16") (pintype "passive"))
      (node (ref "J10") (pin "9") (pinfunction "9_9") (pintype "passive"))
      (node (ref "J11") (pin "10") (pinfunction "10_10") (pintype "passive"))
      (node (ref "J11") (pin "11") (pinfunction "11_11") (pintype "passive"))
      (node (ref "J11") (pin "12") (pinfunction "12_12") (pintype "passive"))
      (node (ref "J11") (pin "13") (pinfunction "13_13") (pintype "passive"))
      (node (ref "J11") (pin "14") (pinfunction "14_14") (pintype "passive"))
      (node (ref "J11") (pin "15") (pinfunction "15_15") (pintype "passive"))
      (node (ref "J11") (pin "16") (pinfunction "16_16") (pintype "passive"))
      (node (ref "J11") (pin "9") (pinfunction "9_9") (pintype "passive"))
      (node (ref "J12") (pin "10") (pinfunction "10_10") (pintype "passive"))
      (node (ref "J12") (pin "11") (pinfunction "11_11") (pintype "passive"))
      (node (ref "J12") (pin "12") (pinfunction "12_12") (pintype "passive"))
      (node (ref "J12") (pin "13") (pinfunction "13_13") (pintype "passive"))
      (node (ref "J12") (pin "14") (pinfunction "14_14") (pintype "passive"))
      (node (ref "J12") (pin "15") (pinfunction "15_15") (pintype "passive"))
      (node (ref "J12") (pin "16") (pinfunction "16_16") (pintype "passive"))
      (node (ref "J12") (pin "9") (pinfunction "9_9") (pintype "passive"))
      (node (ref "J14") (pin "2") (pinfunction "2_2") (pintype "passive"))
      (node (ref "J2") (pin "10") (pinfunction "10_10") (pintype "passive"))
      (node (ref "J2") (pin "11") (pinfunction "11_11") (pintype "passive"))
      (node (ref "J2") (pin "12") (pinfunction "12_12") (pintype "passive"))
      (node (ref "J2") (pin "13") (pinfunction "13_13") (pintype "passive"))
      (node (ref "J2") (pin "14") (pinfunction "14_14") (pintype "passive"))
      (node (ref "J2") (pin "15") (pinfunction "15_15") (pintype "passive"))
      (node (ref "J2") (pin "16") (pinfunction "16_16") (pintype "passive"))
      (node (ref "J2") (pin "9") (pinfunction "9_9") (pintype "passive"))
      (node (ref "J3") (pin "10") (pinfunction "10_10") (pintype "passive"))
      (node (ref "J3") (pin "11") (pinfunction "11_11") (pintype "passive"))
      (node (ref "J3") (pin "12") (pinfunction "12_12") (pintype "passive"))
      (node (ref "J3") (pin "13") (pinfunction "13_13") (pintype "passive"))
      (node (ref "J3") (pin "14") (pinfunction "14_14") (pintype "passive"))
      (node (ref "J3") (pin "15") (pinfunction "15_15") (pintype "passive"))
      (node (ref "J3") (pin "16") (pinfunction "16_16") (pintype "passive"))
      (node (ref "J3") (pin "9") (pinfunction "9_9") (pintype "passive"))
      (node (ref "J4") (pin "10") (pinfunction "10_10") (pintype "passive"))
      (node (ref "J4") (pin "11") (pinfunction "11_11") (pintype "passive"))
      (node (ref "J4") (pin "12") (pinfunction "12_12") (pintype "passive"))
      (node (ref "J4") (pin "13") (pinfunction "13_13") (pintype "passive"))
      (node (ref "J4") (pin "14") (pinfunction "14_14") (pintype "passive"))
      (node (ref "J4") (pin "15") (pinfunction "15_15") (pintype "passive"))
      (node (ref "J4") (pin "16") (pinfunction "16_16") (pintype "passive"))
      (node (ref "J4") (pin "9") (pinfunction "9_9") (pintype "passive"))
      (node (ref "J5") (pin "10") (pinfunction "10_10") (pintype "passive"))
      (node (ref "J5") (pin "11") (pinfunction "11_11") (pintype "passive"))
      (node (ref "J5") (pin "12") (pinfunction "12_12") (pintype "passive"))
      (node (ref "J5") (pin "13") (pinfunction "13_13") (pintype "passive"))
      (node (ref "J5") (pin "14") (pinfunction "14_14") (pintype "passive"))
      (node (ref "J5") (pin "15") (pinfunction "15_15") (pintype "passive"))
      (node (ref "J5") (pin "16") (pinfunction "16_16") (pintype "passive"))
      (node (ref "J5") (pin "9") (pinfunction "9_9") (pintype "passive"))
      (node (ref "J6") (pin "10") (pinfunction "10_10") (pintype "passive"))
      (node (ref "J6") (pin "11") (pinfunction "11_11") (pintype "passive"))
      (node (ref "J6") (pin "12") (pinfunction "12_12") (pintype "passive"))
      (node (ref "J6") (pin "13") (pinfunction "13_13") (pintype "passive"))
      (node (ref "J6") (pin "14") (pinfunction "14_14") (pintype "passive"))
      (node (ref "J6") (pin "15") (pinfunction "15_15") (pintype "passive"))
      (node (ref "J6") (pin "16") (pinfunction "16_16") (pintype "passive"))
      (node (ref "J6") (pin "9") (pinfunction "9_9") (pintype "passive"))
      (node (ref "J7") (pin "10") (pinfunction "10_10") (pintype "passive"))
      (node (ref "J7") (pin "11") (pinfunction "11_11") (pintype "passive"))
      (node (ref "J7") (pin "12") (pinfunction "12_12") (pintype "passive"))
      (node (ref "J7") (pin "13") (pinfunction "13_13") (pintype "passive"))
      (node (ref "J7") (pin "14") (pinfunction "14_14") (pintype "passive"))
      (node (ref "J7") (pin "15") (pinfunction "15_15") (pintype "passive"))
      (node (ref "J7") (pin "16") (pinfunction "16_16") (pintype "passive"))
      (node (ref "J7") (pin "9") (pinfunction "9_9") (pintype "passive"))
      (node (ref "J8") (pin "10") (pinfunction "10_10") (pintype "passive"))
      (node (ref "J8") (pin "11") (pinfunction "11_11") (pintype "passive"))
      (node (ref "J8") (pin "12") (pinfunction "12_12") (pintype "passive"))
      (node (ref "J8") (pin "13") (pinfunction "13_13") (pintype "passive"))
      (node (ref "J8") (pin "14") (pinfunction "14_14") (pintype "passive"))
      (node (ref "J8") (pin "15") (pinfunction "15_15") (pintype "passive"))
      (node (ref "J8") (pin "16") (pinfunction "16_16") (pintype "passive"))
      (node (ref "J8") (pin "9") (pinfunction "9_9") (pintype "passive"))
      (node (ref "J9") (pin "10") (pinfunction "10_10") (pintype "passive"))
      (node (ref "J9") (pin "11") (pinfunction "11_11") (pintype "passive"))
      (node (ref "J9") (pin "12") (pinfunction "12_12") (pintype "passive"))
      (node (ref "J9") (pin "13") (pinfunction "13_13") (pintype "passive"))
      (node (ref "J9") (pin "14") (pinfunction "14_14") (pintype "passive"))
      (node (ref "J9") (pin "15") (pinfunction "15_15") (pintype "passive"))
      (node (ref "J9") (pin "16") (pinfunction "16_16") (pintype "passive"))
      (node (ref "J9") (pin "9") (pinfunction "9_9") (pintype "passive"))
      (node (ref "U$1") (pin "12") (pinfunction "GND_12") (pintype "power_in"))
      (node (ref "U$1") (pin "27") (pinfunction "VSS_27") (pintype "power_in"))
      (node (ref "U$2") (pin "12") (pinfunction "GND_12") (pintype "power_in"))
      (node (ref "U$2") (pin "27") (pinfunction "VSS_27") (pintype "power_in"))
      (node (ref "U$3") (pin "12") (pinfunction "GND_12") (pintype "power_in"))
      (node (ref "U$3") (pin "27") (pinfunction "VSS_27") (pintype "power_in"))
      (node (ref "U$4") (pin "12") (pinfunction "GND_12") (pintype "power_in"))
      (node (ref "U$4") (pin "27") (pinfunction "VSS_27") (pintype "power_in"))
      (node (ref "U$5") (pin "12") (pinfunction "GND_12") (pintype "power_in"))
      (node (ref "U$5") (pin "27") (pinfunction "VSS_27") (pintype "power_in"))
      (node (ref "U$6") (pin "12") (pinfunction "GND_12") (pintype "power_in"))
      (node (ref "U$6") (pin "27") (pinfunction "VSS_27") (pintype "power_in"))
    )
    (net (code "112") (name "Net-(D1-PadA)") (class "Default")
      (node (ref "D1") (pin "A") (pinfunction "A_A") (pintype "passive"))
      (node (ref "J14") (pin "1") (pinfunction "1_1") (pintype "passive"))
    )
    (net (code "113") (name "Net-(D1-PadC)") (class "Default")
      (node (ref "D1") (pin "C") (pinfunction "C_C") (pintype "passive"))
      (node (ref "D2") (pin "C") (pinfunction "C_C") (pintype "passive"))
      (node (ref "XF1") (pin "1") (pinfunction "1_1") (pintype "passive"))
      (node (ref "XF1") (pin "2") (pinfunction "1_2") (pintype "passive"))
    )
    (net (code "114") (name "S0") (class "Default")
      (node (ref "A1") (pin "D2") (pinfunction "D2_D2") (pintype "bidirectional"))
      (node (ref "U$1") (pin "17") (pinfunction "A0_17") (pintype "input"))
      (node (ref "U$2") (pin "17") (pinfunction "A0_17") (pintype "input"))
      (node (ref "U$3") (pin "17") (pinfunction "A0_17") (pintype "input"))
      (node (ref "U$4") (pin "17") (pinfunction "A0_17") (pintype "input"))
      (node (ref "U$5") (pin "17") (pinfunction "A0_17") (pintype "input"))
      (node (ref "U$6") (pin "17") (pinfunction "A0_17") (pintype "input"))
    )
    (net (code "115") (name "S1") (class "Default")
      (node (ref "A1") (pin "D3") (pinfunction "D3_D3") (pintype "bidirectional"))
      (node (ref "U$1") (pin "16") (pinfunction "A1_16") (pintype "input"))
      (node (ref "U$2") (pin "16") (pinfunction "A1_16") (pintype "input"))
      (node (ref "U$3") (pin "16") (pinfunction "A1_16") (pintype "input"))
      (node (ref "U$4") (pin "16") (pinfunction "A1_16") (pintype "input"))
      (node (ref "U$5") (pin "16") (pinfunction "A1_16") (pintype "input"))
      (node (ref "U$6") (pin "16") (pinfunction "A1_16") (pintype "input"))
    )
    (net (code "116") (name "S2") (class "Default")
      (node (ref "A1") (pin "D4") (pinfunction "D4_D4") (pintype "bidirectional"))
      (node (ref "U$1") (pin "15") (pinfunction "A2_15") (pintype "input"))
      (node (ref "U$2") (pin "15") (pinfunction "A2_15") (pintype "input"))
      (node (ref "U$3") (pin "15") (pinfunction "A2_15") (pintype "input"))
      (node (ref "U$4") (pin "15") (pinfunction "A2_15") (pintype "input"))
      (node (ref "U$5") (pin "15") (pinfunction "A2_15") (pintype "input"))
      (node (ref "U$6") (pin "15") (pinfunction "A2_15") (pintype "input"))
    )
    (net (code "117") (name "VBAT") (class "Default")
      (node (ref "A1") (pin "VBAT") (pinfunction "VBAT_VBAT") (pintype "power_in"))
    )
    (net (code "118") (name "unconnected-(A1-(CLK)D13-PadD13)") (class "Default")
      (node (ref "A1") (pin "D13") (pinfunction "(CLK)D13_D13") (pintype "bidirectional"))
    )
    (net (code "119") (name "unconnected-(A1-(CRX1)D0-PadD0)") (class "Default")
      (node (ref "A1") (pin "D0") (pinfunction "(CRX1)D0_D0") (pintype "bidirectional"))
    )
    (net (code "120") (name "unconnected-(A1-(CS)D10-PadD10)") (class "Default")
      (node (ref "A1") (pin "D10") (pinfunction "(CS)D10_D10") (pintype "bidirectional"))
    )
    (net (code "121") (name "unconnected-(A1-(CTX1)D1-PadD1)") (class "Default")
      (node (ref "A1") (pin "D1") (pinfunction "(CTX1)D1_D1") (pintype "bidirectional"))
    )
    (net (code "122") (name "unconnected-(A1-(SDI)D12-PadD12)") (class "Default")
      (node (ref "A1") (pin "D12") (pinfunction "(SDI)D12_D12") (pintype "bidirectional"))
    )
    (net (code "123") (name "unconnected-(A1-(SDO)D11-PadD11)") (class "Default")
      (node (ref "A1") (pin "D11") (pinfunction "(SDO)D11_D11") (pintype "bidirectional"))
    )
    (net (code "124") (name "unconnected-(A1-A12-PadD26)") (class "Default")
      (node (ref "A1") (pin "D26") (pinfunction "A12_D26") (pintype "bidirectional"))
    )
    (net (code "125") (name "unconnected-(A1-A13-PadD27)") (class "Default")
      (node (ref "A1") (pin "D27") (pinfunction "A13_D27") (pintype "bidirectional"))
    )
    (net (code "126") (name "unconnected-(A1-A14-PadD38)") (class "Default")
      (node (ref "A1") (pin "D38") (pinfunction "A14_D38") (pintype "bidirectional"))
    )
    (net (code "127") (name "unconnected-(A1-A15-PadD39)") (class "Default")
      (node (ref "A1") (pin "D39") (pinfunction "A15_D39") (pintype "bidirectional"))
    )
    (net (code "128") (name "unconnected-(A1-A16-PadD40)") (class "Default")
      (node (ref "A1") (pin "D40") (pinfunction "A16_D40") (pintype "bidirectional"))
    )
    (net (code "129") (name "unconnected-(A1-A17-PadD41)") (class "Default")
      (node (ref "A1") (pin "D41") (pinfunction "A17_D41") (pintype "bidirectional"))
    )
    (net (code "130") (name "unconnected-(A1-PadD5)") (class "Default")
      (node (ref "A1") (pin "D5") (pinfunction "D5_D5") (pintype "bidirectional"))
    )
    (net (code "131") (name "unconnected-(A1-PadD6)") (class "Default")
      (node (ref "A1") (pin "D6") (pinfunction "D6_D6") (pintype "bidirectional"))
    )
    (net (code "132") (name "unconnected-(A1-PadD7)") (class "Default")
      (node (ref "A1") (pin "D7") (pinfunction "D7_D7") (pintype "bidirectional"))
    )
    (net (code "133") (name "unconnected-(A1-PadD8)") (class "Default")
      (node (ref "A1") (pin "D8") (pinfunction "D8_D8") (pintype "bidirectional"))
    )
    (net (code "134") (name "unconnected-(A1-PadD9)") (class "Default")
      (node (ref "A1") (pin "D9") (pinfunction "D9_D9") (pintype "bidirectional"))
    )
    (net (code "135") (name "unconnected-(A1-PadD28)") (class "Default")
      (node (ref "A1") (pin "D28") (pinfunction "D28_D28") (pintype "bidirectional"))
    )
    (net (code "136") (name "unconnected-(A1-PadD29)") (class "Default")
      (node (ref "A1") (pin "D29") (pinfunction "D29_D29") (pintype "bidirectional"))
    )
    (net (code "137") (name "unconnected-(A1-PadD30)") (class "Default")
      (node (ref "A1") (pin "D30") (pinfunction "D30_D30") (pintype "bidirectional"))
    )
    (net (code "138") (name "unconnected-(A1-PadD31)") (class "Default")
      (node (ref "A1") (pin "D31") (pinfunction "D31_D31") (pintype "bidirectional"))
    )
    (net (code "139") (name "unconnected-(A1-PadD32)") (class "Default")
      (node (ref "A1") (pin "D32") (pinfunction "D32_D32") (pintype "bidirectional"))
    )
    (net (code "140") (name "unconnected-(A1-PadD33)") (class "Default")
      (node (ref "A1") (pin "D33") (pinfunction "D33_D33") (pintype "bidirectional"))
    )
    (net (code "141") (name "unconnected-(A1-PadD34)") (class "Default")
      (node (ref "A1") (pin "D34") (pinfunction "D34_D34") (pintype "bidirectional"))
    )
    (net (code "142") (name "unconnected-(A1-PadD35)") (class "Default")
      (node (ref "A1") (pin "D35") (pinfunction "D35_D35") (pintype "bidirectional"))
    )
    (net (code "143") (name "unconnected-(A1-PadD36)") (class "Default")
      (node (ref "A1") (pin "D36") (pinfunction "D36_D36") (pintype "bidirectional"))
    )
    (net (code "144") (name "unconnected-(A1-PadD37)") (class "Default")
      (node (ref "A1") (pin "D37") (pinfunction "D37_D37") (pintype "bidirectional"))
    )
    (net (code "145") (name "unconnected-(U$1-NC1-Pad3)") (class "Default")
      (node (ref "U$1") (pin "3") (pinfunction "NC1_3") (pintype "no_connect"))
    )
    (net (code "146") (name "unconnected-(U$1-NC2-Pad14)") (class "Default")
      (node (ref "U$1") (pin "14") (pinfunction "NC2_14") (pintype "no_connect"))
    )
    (net (code "147") (name "unconnected-(U$1-NC3-Pad13)") (class "Default")
      (node (ref "U$1") (pin "13") (pinfunction "NC3_13") (pintype "no_connect"))
    )
    (net (code "148") (name "unconnected-(U$2-NC1-Pad3)") (class "Default")
      (node (ref "U$2") (pin "3") (pinfunction "NC1_3") (pintype "no_connect"))
    )
    (net (code "149") (name "unconnected-(U$2-NC2-Pad14)") (class "Default")
      (node (ref "U$2") (pin "14") (pinfunction "NC2_14") (pintype "no_connect"))
    )
    (net (code "150") (name "unconnected-(U$2-NC3-Pad13)") (class "Default")
      (node (ref "U$2") (pin "13") (pinfunction "NC3_13") (pintype "no_connect"))
    )
    (net (code "151") (name "unconnected-(U$3-NC1-Pad3)") (class "Default")
      (node (ref "U$3") (pin "3") (pinfunction "NC1_3") (pintype "no_connect"))
    )
    (net (code "152") (name "unconnected-(U$3-NC2-Pad14)") (class "Default")
      (node (ref "U$3") (pin "14") (pinfunction "NC2_14") (pintype "no_connect"))
    )
    (net (code "153") (name "unconnected-(U$3-NC3-Pad13)") (class "Default")
      (node (ref "U$3") (pin "13") (pinfunction "NC3_13") (pintype "no_connect"))
    )
    (net (code "154") (name "unconnected-(U$4-NC1-Pad3)") (class "Default")
      (node (ref "U$4") (pin "3") (pinfunction "NC1_3") (pintype "no_connect"))
    )
    (net (code "155") (name "unconnected-(U$4-NC2-Pad14)") (class "Default")
      (node (ref "U$4") (pin "14") (pinfunction "NC2_14") (pintype "no_connect"))
    )
    (net (code "156") (name "unconnected-(U$4-NC3-Pad13)") (class "Default")
      (node (ref "U$4") (pin "13") (pinfunction "NC3_13") (pintype "no_connect"))
    )
    (net (code "157") (name "unconnected-(U$5-NC1-Pad3)") (class "Default")
      (node (ref "U$5") (pin "3") (pinfunction "NC1_3") (pintype "no_connect"))
    )
    (net (code "158") (name "unconnected-(U$5-NC2-Pad14)") (class "Default")
      (node (ref "U$5") (pin "14") (pinfunction "NC2_14") (pintype "no_connect"))
    )
    (net (code "159") (name "unconnected-(U$5-NC3-Pad13)") (class "Default")
      (node (ref "U$5") (pin "13") (pinfunction "NC3_13") (pintype "no_connect"))
    )
    (net (code "160") (name "unconnected-(U$6-NC1-Pad3)") (class "Default")
      (node (ref "U$6") (pin "3") (pinfunction "NC1_3") (pintype "no_connect"))
    )
    (net (code "161") (name "unconnected-(U$6-NC2-Pad14)") (class "Default")
      (node (ref "U$6") (pin "14") (pinfunction "NC2_14") (pintype "no_connect"))
    )
    (net (code "162") (name "unconnected-(U$6-NC3-Pad13)") (class "Default")
      (node (ref "U$6") (pin "13") (pinfunction "NC3_13") (pintype "no_connect"))
    )
  )
)
